# 03fpga.net
KiCad netlist of a schematic drawn in Altium Designer
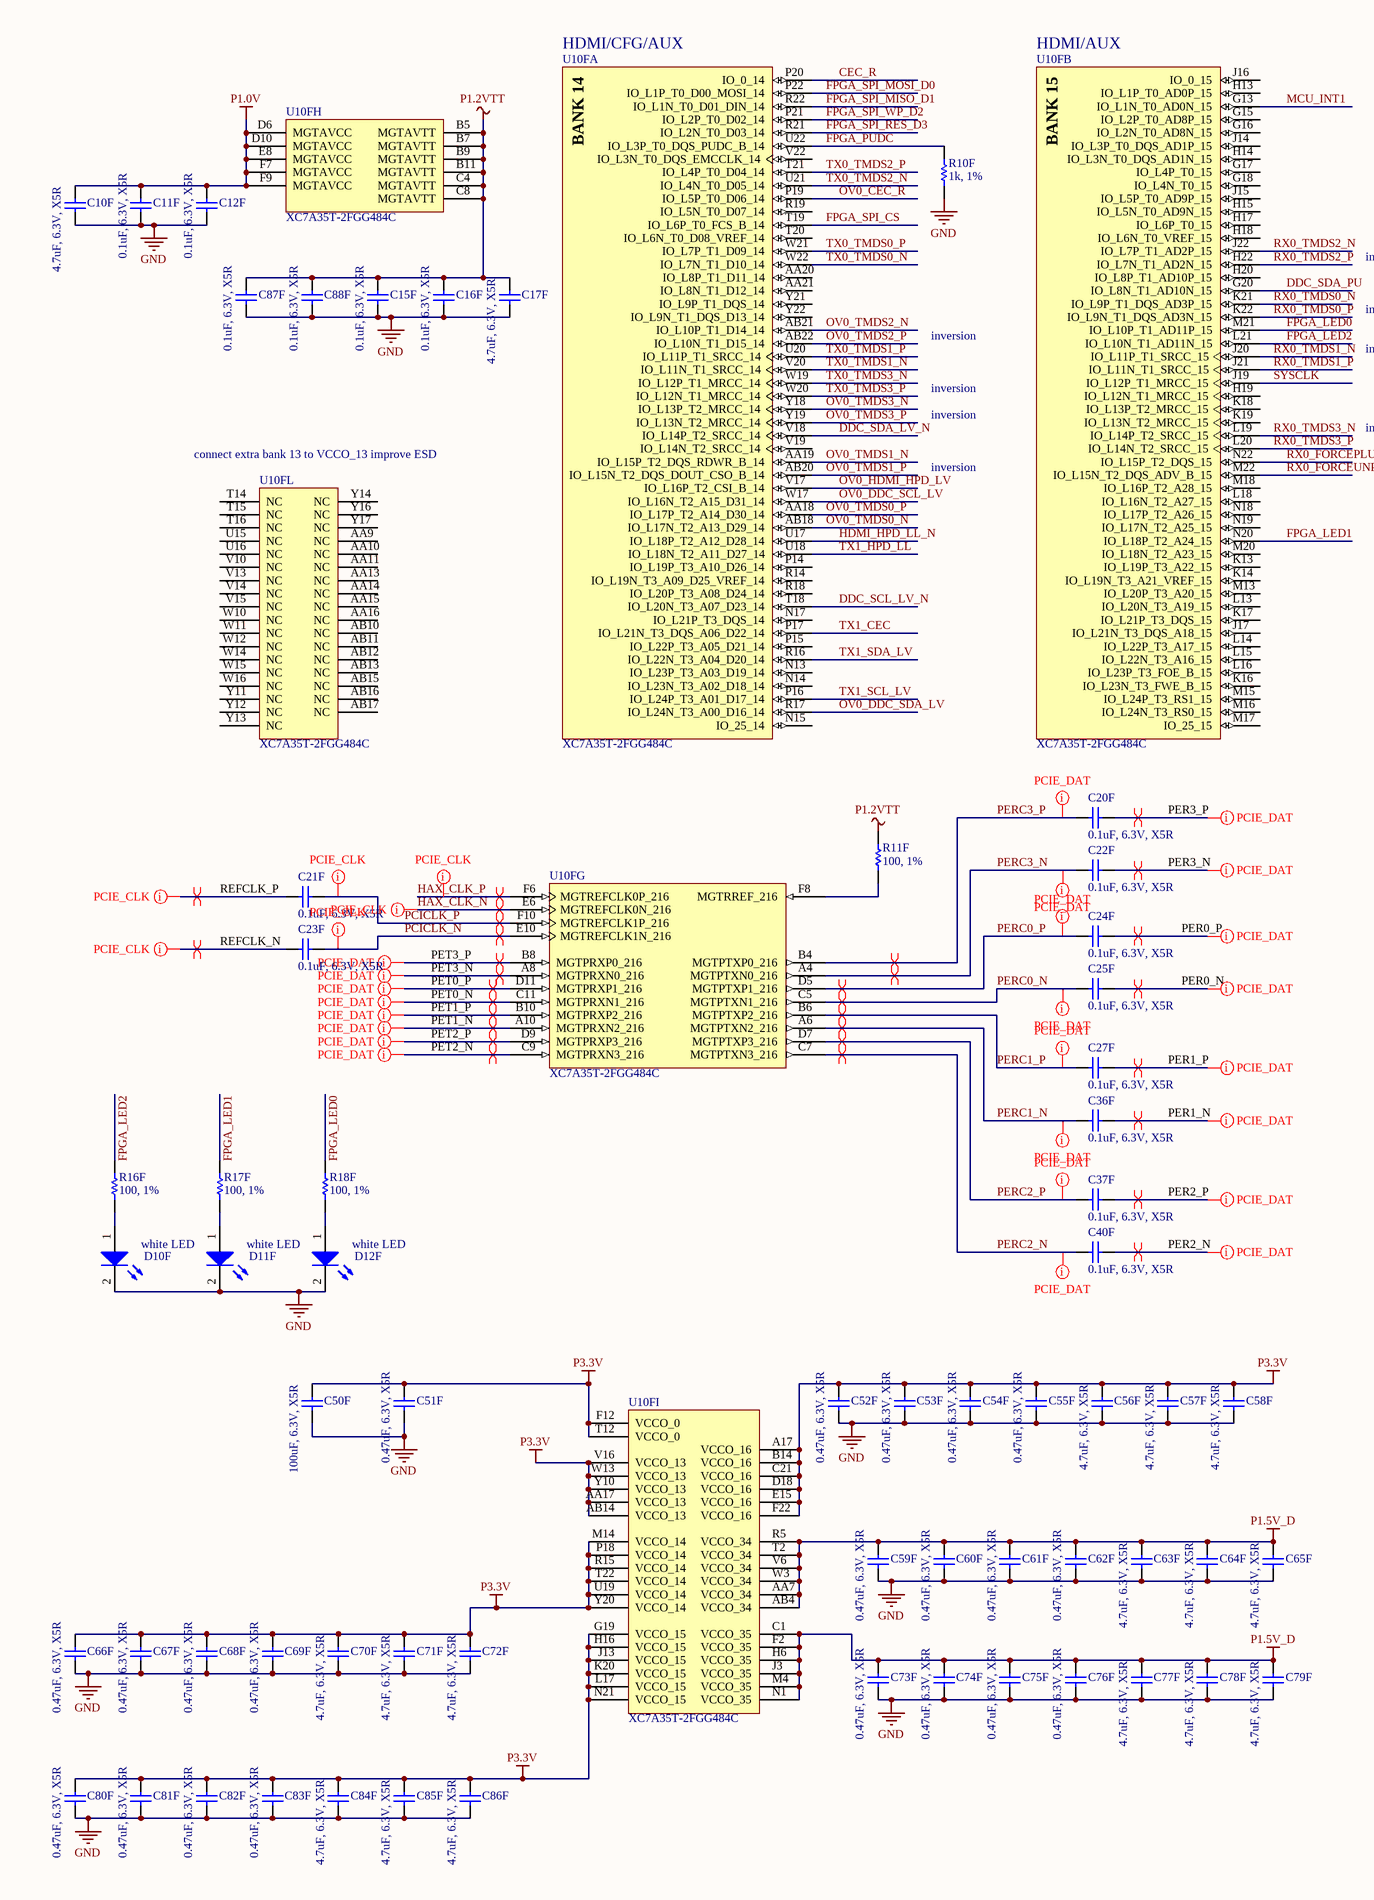
[diagram p0: 03fpga.SchDoc, left]
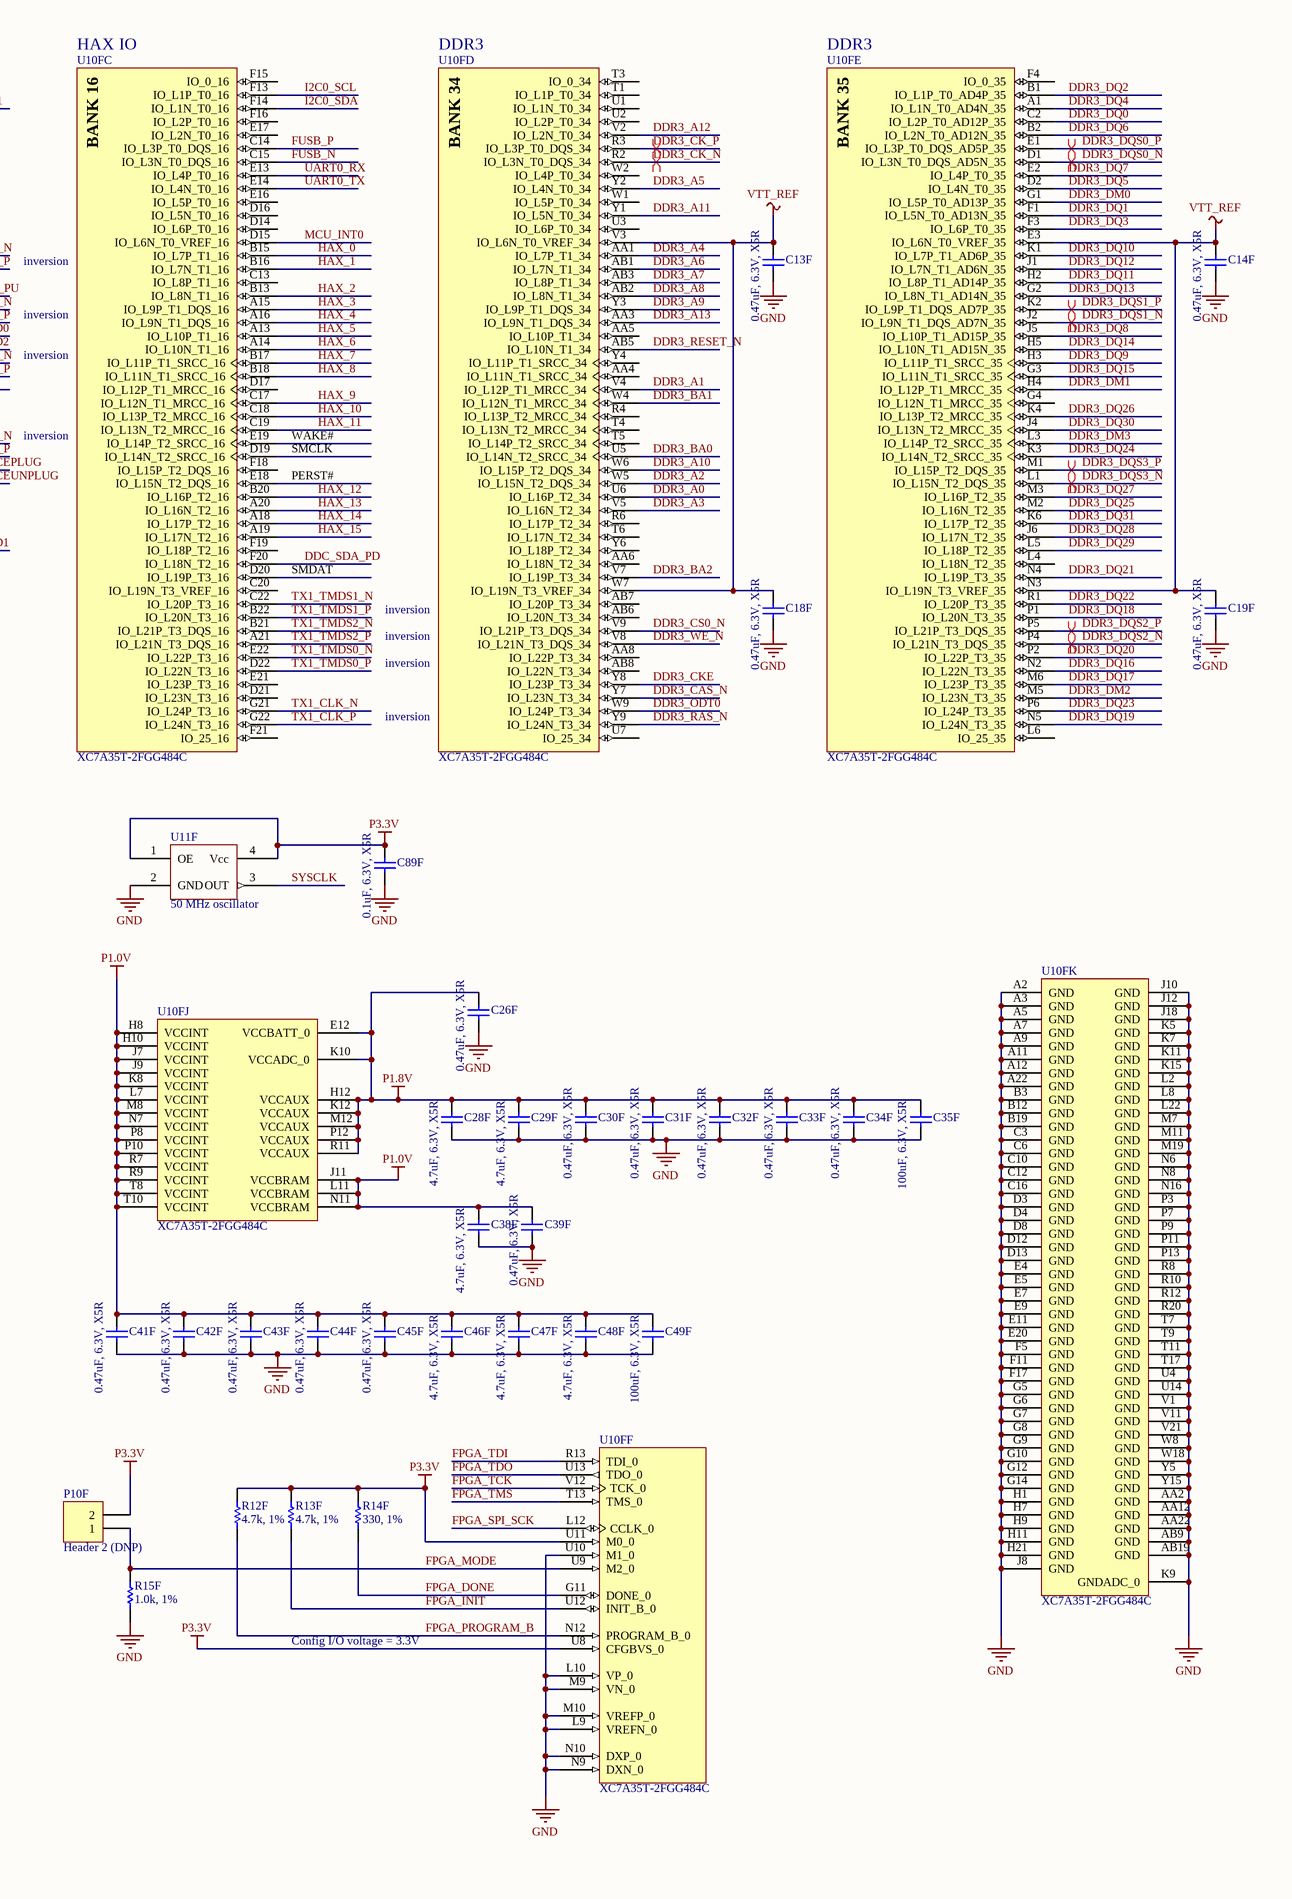
[diagram p1: 03fpga.SchDoc, right]

(export (version "E")
  (design (tool "Eeschema 10.0.6"))
  (components
    (comp (ref "C10F")
      (value "4.7uF, 6.3V, X5R")
      (footprint "CAPC1005N")
      (description "Capacitor (Semiconductor SIM Model)")
      (fields (field (name "MPN") "CL05A475MQ5NQNC"))
      (libsource (lib "Miscellaneous Devices") (part "Cap Semi"))
    )
    (comp (ref "C11F")
      (value "0.1uF, 6.3V, X5R")
      (footprint "CAPC0603X03L")
      (description "Capacitor (Semiconductor SIM Model)")
      (fields (field (name "MPN") "CL03A104KQ3NNNC"))
      (libsource (lib "Miscellaneous Devices") (part "Cap Semi"))
    )
    (comp (ref "C12F")
      (value "0.1uF, 6.3V, X5R")
      (footprint "CAPC0603X03L")
      (description "Capacitor (Semiconductor SIM Model)")
      (fields (field (name "MPN") "CL03A104KQ3NNNC"))
      (libsource (lib "Miscellaneous Devices") (part "Cap Semi"))
    )
    (comp (ref "C13F")
      (value "0.47uF, 6.3V, X5R")
      (footprint "CAPC0603X03L")
      (description "Capacitor (Semiconductor SIM Model)")
      (fields (field (name "MPN") "CL03A474KQ3NNNH"))
      (libsource (lib "Miscellaneous Devices") (part "Cap Semi"))
    )
    (comp (ref "C14F")
      (value "0.47uF, 6.3V, X5R")
      (footprint "CAPC0603X03L")
      (description "Capacitor (Semiconductor SIM Model)")
      (fields (field (name "MPN") "CL03A474KQ3NNNH"))
      (libsource (lib "Miscellaneous Devices") (part "Cap Semi"))
    )
    (comp (ref "C15F")
      (value "0.1uF, 6.3V, X5R")
      (footprint "CAPC0603X03L")
      (description "Capacitor (Semiconductor SIM Model)")
      (fields (field (name "MPN") "CL03A104KQ3NNNC"))
      (libsource (lib "Miscellaneous Devices") (part "Cap Semi"))
    )
    (comp (ref "C16F")
      (value "0.1uF, 6.3V, X5R")
      (footprint "CAPC0603X03L")
      (description "Capacitor (Semiconductor SIM Model)")
      (fields (field (name "MPN") "CL03A104KQ3NNNC"))
      (libsource (lib "Miscellaneous Devices") (part "Cap Semi"))
    )
    (comp (ref "C17F")
      (value "4.7uF, 6.3V, X5R")
      (footprint "CAPC1005N")
      (description "Capacitor (Semiconductor SIM Model)")
      (fields (field (name "MPN") "CL05A475MQ5NQNC"))
      (libsource (lib "Miscellaneous Devices") (part "Cap Semi"))
    )
    (comp (ref "C18F")
      (value "0.47uF, 6.3V, X5R")
      (footprint "CAPC0603X03L")
      (description "Capacitor (Semiconductor SIM Model)")
      (fields (field (name "MPN") "CL03A474KQ3NNNH"))
      (libsource (lib "Miscellaneous Devices") (part "Cap Semi"))
    )
    (comp (ref "C19F")
      (value "0.47uF, 6.3V, X5R")
      (footprint "CAPC0603X03L")
      (description "Capacitor (Semiconductor SIM Model)")
      (fields (field (name "MPN") "CL03A474KQ3NNNH"))
      (libsource (lib "Miscellaneous Devices") (part "Cap Semi"))
    )
    (comp (ref "C20F")
      (value "0.1uF, 6.3V, X5R")
      (footprint "CAPC0603X03L")
      (description "Capacitor (Semiconductor SIM Model)")
      (fields (field (name "MPN") "CL03A104KQ3NNNC"))
      (libsource (lib "Miscellaneous Devices") (part "Cap Semi"))
    )
    (comp (ref "C21F")
      (value "0.1uF, 6.3V, X5R")
      (footprint "CAPC0603X03L")
      (description "Capacitor (Semiconductor SIM Model)")
      (fields (field (name "MPN") "CL03A104KQ3NNNC"))
      (libsource (lib "Miscellaneous Devices") (part "Cap Semi"))
    )
    (comp (ref "C22F")
      (value "0.1uF, 6.3V, X5R")
      (footprint "CAPC0603X03L")
      (description "Capacitor (Semiconductor SIM Model)")
      (fields (field (name "MPN") "CL03A104KQ3NNNC"))
      (libsource (lib "Miscellaneous Devices") (part "Cap Semi"))
    )
    (comp (ref "C23F")
      (value "0.1uF, 6.3V, X5R")
      (footprint "CAPC0603X03L")
      (description "Capacitor (Semiconductor SIM Model)")
      (fields (field (name "MPN") "CL03A104KQ3NNNC"))
      (libsource (lib "Miscellaneous Devices") (part "Cap Semi"))
    )
    (comp (ref "C24F")
      (value "0.1uF, 6.3V, X5R")
      (footprint "CAPC0603X03L")
      (description "Capacitor (Semiconductor SIM Model)")
      (fields (field (name "MPN") "CL03A104KQ3NNNC"))
      (libsource (lib "Miscellaneous Devices") (part "Cap Semi"))
    )
    (comp (ref "C25F")
      (value "0.1uF, 6.3V, X5R")
      (footprint "CAPC0603X03L")
      (description "Capacitor (Semiconductor SIM Model)")
      (fields (field (name "MPN") "CL03A104KQ3NNNC"))
      (libsource (lib "Miscellaneous Devices") (part "Cap Semi"))
    )
    (comp (ref "C26F")
      (value "0.47uF, 6.3V, X5R")
      (footprint "CAPC0603X03L")
      (description "Capacitor (Semiconductor SIM Model)")
      (fields (field (name "MPN") "CL03A474KQ3NNNH"))
      (libsource (lib "Miscellaneous Devices") (part "Cap Semi"))
    )
    (comp (ref "C27F")
      (value "0.1uF, 6.3V, X5R")
      (footprint "CAPC0603X03L")
      (description "Capacitor (Semiconductor SIM Model)")
      (fields (field (name "MPN") "CL03A104KQ3NNNC"))
      (libsource (lib "Miscellaneous Devices") (part "Cap Semi"))
    )
    (comp (ref "C28F")
      (value "4.7uF, 6.3V, X5R")
      (footprint "CAPC1005N")
      (description "Capacitor (Semiconductor SIM Model)")
      (fields (field (name "MPN") "CL05A475MQ5NQNC"))
      (libsource (lib "Miscellaneous Devices") (part "Cap Semi"))
    )
    (comp (ref "C29F")
      (value "4.7uF, 6.3V, X5R")
      (footprint "CAPC1005N")
      (description "Capacitor (Semiconductor SIM Model)")
      (fields (field (name "MPN") "CL05A475MQ5NQNC"))
      (libsource (lib "Miscellaneous Devices") (part "Cap Semi"))
    )
    (comp (ref "C30F")
      (value "0.47uF, 6.3V, X5R")
      (footprint "CAPC0603X03L")
      (description "Capacitor (Semiconductor SIM Model)")
      (fields (field (name "MPN") "CL03A474KQ3NNNH"))
      (libsource (lib "Miscellaneous Devices") (part "Cap Semi"))
    )
    (comp (ref "C31F")
      (value "0.47uF, 6.3V, X5R")
      (footprint "CAPC0603X03L")
      (description "Capacitor (Semiconductor SIM Model)")
      (fields (field (name "MPN") "CL03A474KQ3NNNH"))
      (libsource (lib "Miscellaneous Devices") (part "Cap Semi"))
    )
    (comp (ref "C32F")
      (value "0.47uF, 6.3V, X5R")
      (footprint "CAPC0603X03L")
      (description "Capacitor (Semiconductor SIM Model)")
      (fields (field (name "MPN") "CL03A474KQ3NNNH"))
      (libsource (lib "Miscellaneous Devices") (part "Cap Semi"))
    )
    (comp (ref "C33F")
      (value "0.47uF, 6.3V, X5R")
      (footprint "CAPC0603X03L")
      (description "Capacitor (Semiconductor SIM Model)")
      (fields (field (name "MPN") "CL03A474KQ3NNNH"))
      (libsource (lib "Miscellaneous Devices") (part "Cap Semi"))
    )
    (comp (ref "C34F")
      (value "0.47uF, 6.3V, X5R")
      (footprint "CAPC0603X03L")
      (description "Capacitor (Semiconductor SIM Model)")
      (fields (field (name "MPN") "CL03A474KQ3NNNH"))
      (libsource (lib "Miscellaneous Devices") (part "Cap Semi"))
    )
    (comp (ref "C35F")
      (value "100uF, 6.3V, X5R")
      (footprint "CAPC3216N")
      (description "Capacitor (Semiconductor SIM Model)")
      (fields (field (name "MPN") "CL31A107MQHNNNE"))
      (libsource (lib "Miscellaneous Devices") (part "Cap Semi"))
    )
    (comp (ref "C36F")
      (value "0.1uF, 6.3V, X5R")
      (footprint "CAPC0603X03L")
      (description "Capacitor (Semiconductor SIM Model)")
      (fields (field (name "MPN") "CL03A104KQ3NNNC"))
      (libsource (lib "Miscellaneous Devices") (part "Cap Semi"))
    )
    (comp (ref "C37F")
      (value "0.1uF, 6.3V, X5R")
      (footprint "CAPC0603X03L")
      (description "Capacitor (Semiconductor SIM Model)")
      (fields (field (name "MPN") "CL03A104KQ3NNNC"))
      (libsource (lib "Miscellaneous Devices") (part "Cap Semi"))
    )
    (comp (ref "C38F")
      (value "4.7uF, 6.3V, X5R")
      (footprint "CAPC1005N")
      (description "Capacitor (Semiconductor SIM Model)")
      (fields (field (name "MPN") "CL05A475MQ5NQNC"))
      (libsource (lib "Miscellaneous Devices") (part "Cap Semi"))
    )
    (comp (ref "C39F")
      (value "0.47uF, 6.3V, X5R")
      (footprint "CAPC0603X03L")
      (description "Capacitor (Semiconductor SIM Model)")
      (fields (field (name "MPN") "CL03A474KQ3NNNH"))
      (libsource (lib "Miscellaneous Devices") (part "Cap Semi"))
    )
    (comp (ref "C40F")
      (value "0.1uF, 6.3V, X5R")
      (footprint "CAPC0603X03L")
      (description "Capacitor (Semiconductor SIM Model)")
      (fields (field (name "MPN") "CL03A104KQ3NNNC"))
      (libsource (lib "Miscellaneous Devices") (part "Cap Semi"))
    )
    (comp (ref "C41F")
      (value "0.47uF, 6.3V, X5R")
      (footprint "CAPC0603X03L")
      (description "Capacitor (Semiconductor SIM Model)")
      (fields (field (name "MPN") "CL03A474KQ3NNNH"))
      (libsource (lib "Miscellaneous Devices") (part "Cap Semi"))
    )
    (comp (ref "C42F")
      (value "0.47uF, 6.3V, X5R")
      (footprint "CAPC0603X03L")
      (description "Capacitor (Semiconductor SIM Model)")
      (fields (field (name "MPN") "CL03A474KQ3NNNH"))
      (libsource (lib "Miscellaneous Devices") (part "Cap Semi"))
    )
    (comp (ref "C43F")
      (value "0.47uF, 6.3V, X5R")
      (footprint "CAPC0603X03L")
      (description "Capacitor (Semiconductor SIM Model)")
      (fields (field (name "MPN") "CL03A474KQ3NNNH"))
      (libsource (lib "Miscellaneous Devices") (part "Cap Semi"))
    )
    (comp (ref "C44F")
      (value "0.47uF, 6.3V, X5R")
      (footprint "CAPC0603X03L")
      (description "Capacitor (Semiconductor SIM Model)")
      (fields (field (name "MPN") "CL03A474KQ3NNNH"))
      (libsource (lib "Miscellaneous Devices") (part "Cap Semi"))
    )
    (comp (ref "C45F")
      (value "0.47uF, 6.3V, X5R")
      (footprint "CAPC0603X03L")
      (description "Capacitor (Semiconductor SIM Model)")
      (fields (field (name "MPN") "CL03A474KQ3NNNH"))
      (libsource (lib "Miscellaneous Devices") (part "Cap Semi"))
    )
    (comp (ref "C46F")
      (value "4.7uF, 6.3V, X5R")
      (footprint "CAPC1005N")
      (description "Capacitor (Semiconductor SIM Model)")
      (fields (field (name "MPN") "CL05A475MQ5NQNC"))
      (libsource (lib "Miscellaneous Devices") (part "Cap Semi"))
    )
    (comp (ref "C47F")
      (value "4.7uF, 6.3V, X5R")
      (footprint "CAPC1005N")
      (description "Capacitor (Semiconductor SIM Model)")
      (fields (field (name "MPN") "CL05A475MQ5NQNC"))
      (libsource (lib "Miscellaneous Devices") (part "Cap Semi"))
    )
    (comp (ref "C48F")
      (value "4.7uF, 6.3V, X5R")
      (footprint "CAPC1005N")
      (description "Capacitor (Semiconductor SIM Model)")
      (fields (field (name "MPN") "CL05A475MQ5NQNC"))
      (libsource (lib "Miscellaneous Devices") (part "Cap Semi"))
    )
    (comp (ref "C49F")
      (value "100uF, 6.3V, X5R")
      (footprint "CAPC3216N")
      (description "Capacitor (Semiconductor SIM Model)")
      (fields (field (name "MPN") "CL31A107MQHNNNE"))
      (libsource (lib "Miscellaneous Devices") (part "Cap Semi"))
    )
    (comp (ref "C50F")
      (value "100uF, 6.3V, X5R")
      (footprint "CAPC3216N")
      (description "Capacitor (Semiconductor SIM Model)")
      (fields (field (name "MPN") "CL31A107MQHNNNE"))
      (libsource (lib "Miscellaneous Devices") (part "Cap Semi"))
    )
    (comp (ref "C51F")
      (value "0.47uF, 6.3V, X5R")
      (footprint "CAPC0603X03L")
      (description "Capacitor (Semiconductor SIM Model)")
      (fields (field (name "MPN") "CL03A474KQ3NNNH"))
      (libsource (lib "Miscellaneous Devices") (part "Cap Semi"))
    )
    (comp (ref "C52F")
      (value "0.47uF, 6.3V, X5R")
      (footprint "CAPC0603X03L")
      (description "Capacitor (Semiconductor SIM Model)")
      (fields (field (name "MPN") "CL03A474KQ3NNNH"))
      (libsource (lib "Miscellaneous Devices") (part "Cap Semi"))
    )
    (comp (ref "C53F")
      (value "0.47uF, 6.3V, X5R")
      (footprint "CAPC0603X03L")
      (description "Capacitor (Semiconductor SIM Model)")
      (fields (field (name "MPN") "CL03A474KQ3NNNH"))
      (libsource (lib "Miscellaneous Devices") (part "Cap Semi"))
    )
    (comp (ref "C54F")
      (value "0.47uF, 6.3V, X5R")
      (footprint "CAPC0603X03L")
      (description "Capacitor (Semiconductor SIM Model)")
      (fields (field (name "MPN") "CL03A474KQ3NNNH"))
      (libsource (lib "Miscellaneous Devices") (part "Cap Semi"))
    )
    (comp (ref "C55F")
      (value "0.47uF, 6.3V, X5R")
      (footprint "CAPC0603X03L")
      (description "Capacitor (Semiconductor SIM Model)")
      (fields (field (name "MPN") "CL03A474KQ3NNNH"))
      (libsource (lib "Miscellaneous Devices") (part "Cap Semi"))
    )
    (comp (ref "C56F")
      (value "4.7uF, 6.3V, X5R")
      (footprint "CAPC1005N")
      (description "Capacitor (Semiconductor SIM Model)")
      (fields (field (name "MPN") "CL05A475MQ5NQNC"))
      (libsource (lib "Miscellaneous Devices") (part "Cap Semi"))
    )
    (comp (ref "C57F")
      (value "4.7uF, 6.3V, X5R")
      (footprint "CAPC1005N")
      (description "Capacitor (Semiconductor SIM Model)")
      (fields (field (name "MPN") "CL05A475MQ5NQNC"))
      (libsource (lib "Miscellaneous Devices") (part "Cap Semi"))
    )
    (comp (ref "C58F")
      (value "4.7uF, 6.3V, X5R")
      (footprint "CAPC1005N")
      (description "Capacitor (Semiconductor SIM Model)")
      (fields (field (name "MPN") "CL05A475MQ5NQNC"))
      (libsource (lib "Miscellaneous Devices") (part "Cap Semi"))
    )
    (comp (ref "C59F")
      (value "0.47uF, 6.3V, X5R")
      (footprint "CAPC0603X03L")
      (description "Capacitor (Semiconductor SIM Model)")
      (fields (field (name "MPN") "CL03A474KQ3NNNH"))
      (libsource (lib "Miscellaneous Devices") (part "Cap Semi"))
    )
    (comp (ref "C60F")
      (value "0.47uF, 6.3V, X5R")
      (footprint "CAPC0603X03L")
      (description "Capacitor (Semiconductor SIM Model)")
      (fields (field (name "MPN") "CL03A474KQ3NNNH"))
      (libsource (lib "Miscellaneous Devices") (part "Cap Semi"))
    )
    (comp (ref "C61F")
      (value "0.47uF, 6.3V, X5R")
      (footprint "CAPC0603X03L")
      (description "Capacitor (Semiconductor SIM Model)")
      (fields (field (name "MPN") "CL03A474KQ3NNNH"))
      (libsource (lib "Miscellaneous Devices") (part "Cap Semi"))
    )
    (comp (ref "C62F")
      (value "0.47uF, 6.3V, X5R")
      (footprint "CAPC0603X03L")
      (description "Capacitor (Semiconductor SIM Model)")
      (fields (field (name "MPN") "CL03A474KQ3NNNH"))
      (libsource (lib "Miscellaneous Devices") (part "Cap Semi"))
    )
    (comp (ref "C63F")
      (value "4.7uF, 6.3V, X5R")
      (footprint "CAPC1005N")
      (description "Capacitor (Semiconductor SIM Model)")
      (fields (field (name "MPN") "CL05A475MQ5NQNC"))
      (libsource (lib "Miscellaneous Devices") (part "Cap Semi"))
    )
    (comp (ref "C64F")
      (value "4.7uF, 6.3V, X5R")
      (footprint "CAPC1005N")
      (description "Capacitor (Semiconductor SIM Model)")
      (fields (field (name "MPN") "CL05A475MQ5NQNC"))
      (libsource (lib "Miscellaneous Devices") (part "Cap Semi"))
    )
    (comp (ref "C65F")
      (value "4.7uF, 6.3V, X5R")
      (footprint "CAPC1005N")
      (description "Capacitor (Semiconductor SIM Model)")
      (fields (field (name "MPN") "CL05A475MQ5NQNC"))
      (libsource (lib "Miscellaneous Devices") (part "Cap Semi"))
    )
    (comp (ref "C66F")
      (value "0.47uF, 6.3V, X5R")
      (footprint "CAPC0603X03L")
      (description "Capacitor (Semiconductor SIM Model)")
      (fields (field (name "MPN") "CL03A474KQ3NNNH"))
      (libsource (lib "Miscellaneous Devices") (part "Cap Semi"))
    )
    (comp (ref "C67F")
      (value "0.47uF, 6.3V, X5R")
      (footprint "CAPC0603X03L")
      (description "Capacitor (Semiconductor SIM Model)")
      (fields (field (name "MPN") "CL03A474KQ3NNNH"))
      (libsource (lib "Miscellaneous Devices") (part "Cap Semi"))
    )
    (comp (ref "C68F")
      (value "0.47uF, 6.3V, X5R")
      (footprint "CAPC0603X03L")
      (description "Capacitor (Semiconductor SIM Model)")
      (fields (field (name "MPN") "CL03A474KQ3NNNH"))
      (libsource (lib "Miscellaneous Devices") (part "Cap Semi"))
    )
    (comp (ref "C69F")
      (value "0.47uF, 6.3V, X5R")
      (footprint "CAPC0603X03L")
      (description "Capacitor (Semiconductor SIM Model)")
      (fields (field (name "MPN") "CL03A474KQ3NNNH"))
      (libsource (lib "Miscellaneous Devices") (part "Cap Semi"))
    )
    (comp (ref "C70F")
      (value "4.7uF, 6.3V, X5R")
      (footprint "CAPC1005N")
      (description "Capacitor (Semiconductor SIM Model)")
      (fields (field (name "MPN") "CL05A475MQ5NQNC"))
      (libsource (lib "Miscellaneous Devices") (part "Cap Semi"))
    )
    (comp (ref "C71F")
      (value "4.7uF, 6.3V, X5R")
      (footprint "CAPC1005N")
      (description "Capacitor (Semiconductor SIM Model)")
      (fields (field (name "MPN") "CL05A475MQ5NQNC"))
      (libsource (lib "Miscellaneous Devices") (part "Cap Semi"))
    )
    (comp (ref "C72F")
      (value "4.7uF, 6.3V, X5R")
      (footprint "CAPC1005N")
      (description "Capacitor (Semiconductor SIM Model)")
      (fields (field (name "MPN") "CL05A475MQ5NQNC"))
      (libsource (lib "Miscellaneous Devices") (part "Cap Semi"))
    )
    (comp (ref "C73F")
      (value "0.47uF, 6.3V, X5R")
      (footprint "CAPC0603X03L")
      (description "Capacitor (Semiconductor SIM Model)")
      (fields (field (name "MPN") "CL03A474KQ3NNNH"))
      (libsource (lib "Miscellaneous Devices") (part "Cap Semi"))
    )
    (comp (ref "C74F")
      (value "0.47uF, 6.3V, X5R")
      (footprint "CAPC0603X03L")
      (description "Capacitor (Semiconductor SIM Model)")
      (fields (field (name "MPN") "CL03A474KQ3NNNH"))
      (libsource (lib "Miscellaneous Devices") (part "Cap Semi"))
    )
    (comp (ref "C75F")
      (value "0.47uF, 6.3V, X5R")
      (footprint "CAPC0603X03L")
      (description "Capacitor (Semiconductor SIM Model)")
      (fields (field (name "MPN") "CL03A474KQ3NNNH"))
      (libsource (lib "Miscellaneous Devices") (part "Cap Semi"))
    )
    (comp (ref "C76F")
      (value "0.47uF, 6.3V, X5R")
      (footprint "CAPC0603X03L")
      (description "Capacitor (Semiconductor SIM Model)")
      (fields (field (name "MPN") "CL03A474KQ3NNNH"))
      (libsource (lib "Miscellaneous Devices") (part "Cap Semi"))
    )
    (comp (ref "C77F")
      (value "4.7uF, 6.3V, X5R")
      (footprint "CAPC1005N")
      (description "Capacitor (Semiconductor SIM Model)")
      (fields (field (name "MPN") "CL05A475MQ5NQNC"))
      (libsource (lib "Miscellaneous Devices") (part "Cap Semi"))
    )
    (comp (ref "C78F")
      (value "4.7uF, 6.3V, X5R")
      (footprint "CAPC1005N")
      (description "Capacitor (Semiconductor SIM Model)")
      (fields (field (name "MPN") "CL05A475MQ5NQNC"))
      (libsource (lib "Miscellaneous Devices") (part "Cap Semi"))
    )
    (comp (ref "C79F")
      (value "4.7uF, 6.3V, X5R")
      (footprint "CAPC1005N")
      (description "Capacitor (Semiconductor SIM Model)")
      (fields (field (name "MPN") "CL05A475MQ5NQNC"))
      (libsource (lib "Miscellaneous Devices") (part "Cap Semi"))
    )
    (comp (ref "C80F")
      (value "0.47uF, 6.3V, X5R")
      (footprint "CAPC0603X03L")
      (description "Capacitor (Semiconductor SIM Model)")
      (fields (field (name "MPN") "CL03A474KQ3NNNH"))
      (libsource (lib "Miscellaneous Devices") (part "Cap Semi"))
    )
    (comp (ref "C81F")
      (value "0.47uF, 6.3V, X5R")
      (footprint "CAPC0603X03L")
      (description "Capacitor (Semiconductor SIM Model)")
      (fields (field (name "MPN") "CL03A474KQ3NNNH"))
      (libsource (lib "Miscellaneous Devices") (part "Cap Semi"))
    )
    (comp (ref "C82F")
      (value "0.47uF, 6.3V, X5R")
      (footprint "CAPC0603X03L")
      (description "Capacitor (Semiconductor SIM Model)")
      (fields (field (name "MPN") "CL03A474KQ3NNNH"))
      (libsource (lib "Miscellaneous Devices") (part "Cap Semi"))
    )
    (comp (ref "C83F")
      (value "0.47uF, 6.3V, X5R")
      (footprint "CAPC0603X03L")
      (description "Capacitor (Semiconductor SIM Model)")
      (fields (field (name "MPN") "CL03A474KQ3NNNH"))
      (libsource (lib "Miscellaneous Devices") (part "Cap Semi"))
    )
    (comp (ref "C84F")
      (value "4.7uF, 6.3V, X5R")
      (footprint "CAPC1005N")
      (description "Capacitor (Semiconductor SIM Model)")
      (fields (field (name "MPN") "CL05A475MQ5NQNC"))
      (libsource (lib "Miscellaneous Devices") (part "Cap Semi"))
    )
    (comp (ref "C85F")
      (value "4.7uF, 6.3V, X5R")
      (footprint "CAPC1005N")
      (description "Capacitor (Semiconductor SIM Model)")
      (fields (field (name "MPN") "CL05A475MQ5NQNC"))
      (libsource (lib "Miscellaneous Devices") (part "Cap Semi"))
    )
    (comp (ref "C86F")
      (value "4.7uF, 6.3V, X5R")
      (footprint "CAPC1005N")
      (description "Capacitor (Semiconductor SIM Model)")
      (fields (field (name "MPN") "CL05A475MQ5NQNC"))
      (libsource (lib "Miscellaneous Devices") (part "Cap Semi"))
    )
    (comp (ref "C87F")
      (value "0.1uF, 6.3V, X5R")
      (footprint "CAPC0603X03L")
      (description "Capacitor (Semiconductor SIM Model)")
      (fields (field (name "MPN") "CL03A104KQ3NNNC"))
      (libsource (lib "Miscellaneous Devices") (part "Cap Semi"))
    )
    (comp (ref "C88F")
      (value "0.1uF, 6.3V, X5R")
      (footprint "CAPC0603X03L")
      (description "Capacitor (Semiconductor SIM Model)")
      (fields (field (name "MPN") "CL03A104KQ3NNNC"))
      (libsource (lib "Miscellaneous Devices") (part "Cap Semi"))
    )
    (comp (ref "C89F")
      (value "0.1uF, 6.3V, X5R")
      (footprint "CAPC0603X03L")
      (description "Capacitor (Semiconductor SIM Model)")
      (fields (field (name "MPN") "CL03A104KQ3NNNC"))
      (libsource (lib "Miscellaneous Devices") (part "Cap Semi"))
    )
    (comp (ref "D10F")
      (value "white LED")
      (footprint "CD2012-0805")
      (description "Typical RED, GREEN, YELLOW, AMBER GaAs LED")
      (fields (field (name "MPN") "CB-2012QWC-P8"))
      (libsource (lib "Miscellaneous Devices") (part "LED2"))
    )
    (comp (ref "D11F")
      (value "white LED")
      (footprint "CD2012-0805")
      (description "Typical RED, GREEN, YELLOW, AMBER GaAs LED")
      (fields (field (name "MPN") "CB-2012QWC-P8"))
      (libsource (lib "Miscellaneous Devices") (part "LED2"))
    )
    (comp (ref "D12F")
      (value "white LED")
      (footprint "CD2012-0805")
      (description "Typical RED, GREEN, YELLOW, AMBER GaAs LED")
      (fields (field (name "MPN") "CB-2012QWC-P8"))
      (libsource (lib "Miscellaneous Devices") (part "LED2"))
    )
    (comp (ref "P10F")
      (value "Header 2 (DNP)")
      (footprint "HDR1X2")
      (description "Header, 2-Pin")
      (fields (field (name "MPN") "DNP") (field (name "PUBLISHER") "Altium Limited"))
      (libsource (lib "Miscellaneous Connectors") (part "Header 2"))
    )
    (comp (ref "R10F")
      (value "1k, 1%")
      (footprint "RESC1005N")
      (description "Resistor")
      (fields (field (name "MPN") "RS02U102FT"))
      (libsource (lib "Miscellaneous Devices") (part "Res1"))
    )
    (comp (ref "R11F")
      (value "100, 1%")
      (footprint "RESC1005N")
      (description "Resistor")
      (fields (field (name "MPN") "ANY"))
      (libsource (lib "Miscellaneous Devices") (part "Res1"))
    )
    (comp (ref "R12F")
      (value "4.7k, 1%")
      (footprint "RESC1005N")
      (description "Resistor")
      (fields (field (name "MPN") "ANY"))
      (libsource (lib "Miscellaneous Devices") (part "Res1"))
    )
    (comp (ref "R13F")
      (value "4.7k, 1%")
      (footprint "RESC1005N")
      (description "Resistor")
      (fields (field (name "MPN") "ANY"))
      (libsource (lib "Miscellaneous Devices") (part "Res1"))
    )
    (comp (ref "R14F")
      (value "330, 1%")
      (footprint "RESC1005N")
      (description "Resistor")
      (fields (field (name "MPN") "RS02U331FT"))
      (libsource (lib "Miscellaneous Devices") (part "Res1"))
    )
    (comp (ref "R15F")
      (value "1.0k, 1%")
      (footprint "RESC1005N")
      (description "Resistor")
      (fields (field (name "MPN") "ANY"))
      (libsource (lib "Miscellaneous Devices") (part "Res1"))
    )
    (comp (ref "R16F")
      (value "100, 1%")
      (footprint "RESC1005N")
      (description "Resistor")
      (fields (field (name "MPN") "RS02U101FT"))
      (libsource (lib "Miscellaneous Devices") (part "Res1"))
    )
    (comp (ref "R17F")
      (value "100, 1%")
      (footprint "RESC1005N")
      (description "Resistor")
      (fields (field (name "MPN") "RS02U101FT"))
      (libsource (lib "Miscellaneous Devices") (part "Res1"))
    )
    (comp (ref "R18F")
      (value "100, 1%")
      (footprint "RESC1005N")
      (description "Resistor")
      (fields (field (name "MPN") "RS02U101FT"))
      (libsource (lib "Miscellaneous Devices") (part "Res1"))
    )
    (comp (ref "U10F")
      (value "XC7A35T-2FGG484C")
      (footprint "FGG484")
      (description "Artix-7 FPGA, 250 User I/Os, 4 GTP, 484-Ball BGA, Speed Grade 2, Commercial Grade, Pb-Free")
      (fields (field (name "MANUFACTURER") "Xilinx"))
      (libsource (lib "Xilinx Artix-7") (part "XC7A35T-2FGG484C"))
    )
    (comp (ref "U11F")
      (value "50 MHz oscillator")
      (footprint "ABRACON_ASDMB")
      (description "Abracon ASDMB Miniature Oscillator")
      (fields (field (name "MPN") "ASDMB-50.000MHZ-LC-T"))
      (libsource (lib "commonsch") (part "OSCILLATOR"))
    )
  )
  (nets
    (net (code "1") (name "/CEC_R") (class "Default")
      (node (ref "U10F") (pin "P20") (pinfunction "IO_0_14_P20") (pintype "bidirectional"))
    )
    (net (code "2") (name "/DDC_SCL_LV_N") (class "Default")
      (node (ref "U10F") (pin "T18") (pinfunction "IO_L20N_T3_A07_D23_14_T18") (pintype "bidirectional"))
    )
    (net (code "3") (name "/DDC_SDA_LV_N") (class "Default")
      (node (ref "U10F") (pin "V18") (pinfunction "IO_L14P_T2_SRCC_14_V18") (pintype "bidirectional"))
    )
    (net (code "4") (name "/DDC_SDA_PD") (class "Default")
      (node (ref "U10F") (pin "F20") (pinfunction "IO_L18N_T2_16_F20") (pintype "bidirectional"))
    )
    (net (code "5") (name "/DDC_SDA_PU") (class "Default")
      (node (ref "U10F") (pin "G20") (pinfunction "IO_L8N_T1_AD10N_15_G20") (pintype "bidirectional"))
    )
    (net (code "6") (name "/DDR3_A0") (class "Default")
      (node (ref "U10F") (pin "U6") (pinfunction "IO_L16P_T2_34_U6") (pintype "bidirectional"))
    )
    (net (code "7") (name "/DDR3_A1") (class "Default")
      (node (ref "U10F") (pin "V4") (pinfunction "IO_L12P_T1_MRCC_34_V4") (pintype "bidirectional"))
    )
    (net (code "8") (name "/DDR3_A2") (class "Default")
      (node (ref "U10F") (pin "W5") (pinfunction "IO_L15N_T2_DQS_34_W5") (pintype "bidirectional"))
    )
    (net (code "9") (name "/DDR3_A3") (class "Default")
      (node (ref "U10F") (pin "V5") (pinfunction "IO_L16N_T2_34_V5") (pintype "bidirectional"))
    )
    (net (code "10") (name "/DDR3_A4") (class "Default")
      (node (ref "U10F") (pin "AA1") (pinfunction "IO_L7P_T1_34_AA1") (pintype "bidirectional"))
    )
    (net (code "11") (name "/DDR3_A5") (class "Default")
      (node (ref "U10F") (pin "Y2") (pinfunction "IO_L4N_T0_34_Y2") (pintype "bidirectional"))
    )
    (net (code "12") (name "/DDR3_A6") (class "Default")
      (node (ref "U10F") (pin "AB1") (pinfunction "IO_L7N_T1_34_AB1") (pintype "bidirectional"))
    )
    (net (code "13") (name "/DDR3_A7") (class "Default")
      (node (ref "U10F") (pin "AB3") (pinfunction "IO_L8P_T1_34_AB3") (pintype "bidirectional"))
    )
    (net (code "14") (name "/DDR3_A8") (class "Default")
      (node (ref "U10F") (pin "AB2") (pinfunction "IO_L8N_T1_34_AB2") (pintype "bidirectional"))
    )
    (net (code "15") (name "/DDR3_A9") (class "Default")
      (node (ref "U10F") (pin "Y3") (pinfunction "IO_L9P_T1_DQS_34_Y3") (pintype "bidirectional"))
    )
    (net (code "16") (name "/DDR3_A10") (class "Default")
      (node (ref "U10F") (pin "W6") (pinfunction "IO_L15P_T2_DQS_34_W6") (pintype "bidirectional"))
    )
    (net (code "17") (name "/DDR3_A11") (class "Default")
      (node (ref "U10F") (pin "Y1") (pinfunction "IO_L5N_T0_34_Y1") (pintype "bidirectional"))
    )
    (net (code "18") (name "/DDR3_A12") (class "Default")
      (node (ref "U10F") (pin "V2") (pinfunction "IO_L2N_T0_34_V2") (pintype "bidirectional"))
    )
    (net (code "19") (name "/DDR3_A13") (class "Default")
      (node (ref "U10F") (pin "AA3") (pinfunction "IO_L9N_T1_DQS_34_AA3") (pintype "bidirectional"))
    )
    (net (code "20") (name "/DDR3_BA0") (class "Default")
      (node (ref "U10F") (pin "U5") (pinfunction "IO_L14N_T2_SRCC_34_U5") (pintype "bidirectional"))
    )
    (net (code "21") (name "/DDR3_BA1") (class "Default")
      (node (ref "U10F") (pin "W4") (pinfunction "IO_L12N_T1_MRCC_34_W4") (pintype "bidirectional"))
    )
    (net (code "22") (name "/DDR3_BA2") (class "Default")
      (node (ref "U10F") (pin "V7") (pinfunction "IO_L19P_T3_34_V7") (pintype "bidirectional"))
    )
    (net (code "23") (name "/DDR3_CAS_N") (class "Default")
      (node (ref "U10F") (pin "Y7") (pinfunction "IO_L23N_T3_34_Y7") (pintype "bidirectional"))
    )
    (net (code "24") (name "/DDR3_CKE") (class "Default")
      (node (ref "U10F") (pin "Y8") (pinfunction "IO_L23P_T3_34_Y8") (pintype "bidirectional"))
    )
    (net (code "25") (name "/DDR3_CK_N") (class "Default")
      (node (ref "U10F") (pin "R2") (pinfunction "IO_L3N_T0_DQS_34_R2") (pintype "bidirectional"))
    )
    (net (code "26") (name "/DDR3_CK_P") (class "Default")
      (node (ref "U10F") (pin "R3") (pinfunction "IO_L3P_T0_DQS_34_R3") (pintype "bidirectional"))
    )
    (net (code "27") (name "/DDR3_CS0_N") (class "Default")
      (node (ref "U10F") (pin "V9") (pinfunction "IO_L21P_T3_DQS_34_V9") (pintype "bidirectional"))
    )
    (net (code "28") (name "/DDR3_DM0") (class "Default")
      (node (ref "U10F") (pin "G1") (pinfunction "IO_L5P_T0_AD13P_35_G1") (pintype "bidirectional"))
    )
    (net (code "29") (name "/DDR3_DM1") (class "Default")
      (node (ref "U10F") (pin "H4") (pinfunction "IO_L12P_T1_MRCC_35_H4") (pintype "bidirectional"))
    )
    (net (code "30") (name "/DDR3_DM2") (class "Default")
      (node (ref "U10F") (pin "M5") (pinfunction "IO_L23N_T3_35_M5") (pintype "bidirectional"))
    )
    (net (code "31") (name "/DDR3_DM3") (class "Default")
      (node (ref "U10F") (pin "L3") (pinfunction "IO_L14P_T2_SRCC_35_L3") (pintype "bidirectional"))
    )
    (net (code "32") (name "/DDR3_DQ0") (class "Default")
      (node (ref "U10F") (pin "C2") (pinfunction "IO_L2P_T0_AD12P_35_C2") (pintype "bidirectional"))
    )
    (net (code "33") (name "/DDR3_DQ1") (class "Default")
      (node (ref "U10F") (pin "F1") (pinfunction "IO_L5N_T0_AD13N_35_F1") (pintype "bidirectional"))
    )
    (net (code "34") (name "/DDR3_DQ2") (class "Default")
      (node (ref "U10F") (pin "B1") (pinfunction "IO_L1P_T0_AD4P_35_B1") (pintype "bidirectional"))
    )
    (net (code "35") (name "/DDR3_DQ3") (class "Default")
      (node (ref "U10F") (pin "F3") (pinfunction "IO_L6P_T0_35_F3") (pintype "bidirectional"))
    )
    (net (code "36") (name "/DDR3_DQ4") (class "Default")
      (node (ref "U10F") (pin "A1") (pinfunction "IO_L1N_T0_AD4N_35_A1") (pintype "bidirectional"))
    )
    (net (code "37") (name "/DDR3_DQ5") (class "Default")
      (node (ref "U10F") (pin "D2") (pinfunction "IO_L4N_T0_35_D2") (pintype "bidirectional"))
    )
    (net (code "38") (name "/DDR3_DQ6") (class "Default")
      (node (ref "U10F") (pin "B2") (pinfunction "IO_L2N_T0_AD12N_35_B2") (pintype "bidirectional"))
    )
    (net (code "39") (name "/DDR3_DQ7") (class "Default")
      (node (ref "U10F") (pin "E2") (pinfunction "IO_L4P_T0_35_E2") (pintype "bidirectional"))
    )
    (net (code "40") (name "/DDR3_DQ8") (class "Default")
      (node (ref "U10F") (pin "J5") (pinfunction "IO_L10P_T1_AD15P_35_J5") (pintype "bidirectional"))
    )
    (net (code "41") (name "/DDR3_DQ9") (class "Default")
      (node (ref "U10F") (pin "H3") (pinfunction "IO_L11P_T1_SRCC_35_H3") (pintype "bidirectional"))
    )
    (net (code "42") (name "/DDR3_DQ10") (class "Default")
      (node (ref "U10F") (pin "K1") (pinfunction "IO_L7P_T1_AD6P_35_K1") (pintype "bidirectional"))
    )
    (net (code "43") (name "/DDR3_DQ11") (class "Default")
      (node (ref "U10F") (pin "H2") (pinfunction "IO_L8P_T1_AD14P_35_H2") (pintype "bidirectional"))
    )
    (net (code "44") (name "/DDR3_DQ12") (class "Default")
      (node (ref "U10F") (pin "J1") (pinfunction "IO_L7N_T1_AD6N_35_J1") (pintype "bidirectional"))
    )
    (net (code "45") (name "/DDR3_DQ13") (class "Default")
      (node (ref "U10F") (pin "G2") (pinfunction "IO_L8N_T1_AD14N_35_G2") (pintype "bidirectional"))
    )
    (net (code "46") (name "/DDR3_DQ14") (class "Default")
      (node (ref "U10F") (pin "H5") (pinfunction "IO_L10N_T1_AD15N_35_H5") (pintype "bidirectional"))
    )
    (net (code "47") (name "/DDR3_DQ15") (class "Default")
      (node (ref "U10F") (pin "G3") (pinfunction "IO_L11N_T1_SRCC_35_G3") (pintype "bidirectional"))
    )
    (net (code "48") (name "/DDR3_DQ16") (class "Default")
      (node (ref "U10F") (pin "N2") (pinfunction "IO_L22N_T3_35_N2") (pintype "bidirectional"))
    )
    (net (code "49") (name "/DDR3_DQ17") (class "Default")
      (node (ref "U10F") (pin "M6") (pinfunction "IO_L23P_T3_35_M6") (pintype "bidirectional"))
    )
    (net (code "50") (name "/DDR3_DQ18") (class "Default")
      (node (ref "U10F") (pin "P1") (pinfunction "IO_L20N_T3_35_P1") (pintype "bidirectional"))
    )
    (net (code "51") (name "/DDR3_DQ19") (class "Default")
      (node (ref "U10F") (pin "N5") (pinfunction "IO_L24N_T3_35_N5") (pintype "bidirectional"))
    )
    (net (code "52") (name "/DDR3_DQ20") (class "Default")
      (node (ref "U10F") (pin "P2") (pinfunction "IO_L22P_T3_35_P2") (pintype "bidirectional"))
    )
    (net (code "53") (name "/DDR3_DQ21") (class "Default")
      (node (ref "U10F") (pin "N4") (pinfunction "IO_L19P_T3_35_N4") (pintype "bidirectional"))
    )
    (net (code "54") (name "/DDR3_DQ22") (class "Default")
      (node (ref "U10F") (pin "R1") (pinfunction "IO_L20P_T3_35_R1") (pintype "bidirectional"))
    )
    (net (code "55") (name "/DDR3_DQ23") (class "Default")
      (node (ref "U10F") (pin "P6") (pinfunction "IO_L24P_T3_35_P6") (pintype "bidirectional"))
    )
    (net (code "56") (name "/DDR3_DQ24") (class "Default")
      (node (ref "U10F") (pin "K3") (pinfunction "IO_L14N_T2_SRCC_35_K3") (pintype "bidirectional"))
    )
    (net (code "57") (name "/DDR3_DQ25") (class "Default")
      (node (ref "U10F") (pin "M2") (pinfunction "IO_L16N_T2_35_M2") (pintype "bidirectional"))
    )
    (net (code "58") (name "/DDR3_DQ26") (class "Default")
      (node (ref "U10F") (pin "K4") (pinfunction "IO_L13P_T2_MRCC_35_K4") (pintype "bidirectional"))
    )
    (net (code "59") (name "/DDR3_DQ27") (class "Default")
      (node (ref "U10F") (pin "M3") (pinfunction "IO_L16P_T2_35_M3") (pintype "bidirectional"))
    )
    (net (code "60") (name "/DDR3_DQ28") (class "Default")
      (node (ref "U10F") (pin "J6") (pinfunction "IO_L17N_T2_35_J6") (pintype "bidirectional"))
    )
    (net (code "61") (name "/DDR3_DQ29") (class "Default")
      (node (ref "U10F") (pin "L5") (pinfunction "IO_L18P_T2_35_L5") (pintype "bidirectional"))
    )
    (net (code "62") (name "/DDR3_DQ30") (class "Default")
      (node (ref "U10F") (pin "J4") (pinfunction "IO_L13N_T2_MRCC_35_J4") (pintype "bidirectional"))
    )
    (net (code "63") (name "/DDR3_DQ31") (class "Default")
      (node (ref "U10F") (pin "K6") (pinfunction "IO_L17P_T2_35_K6") (pintype "bidirectional"))
    )
    (net (code "64") (name "/DDR3_DQS0_N") (class "Default")
      (node (ref "U10F") (pin "D1") (pinfunction "IO_L3N_T0_DQS_AD5N_35_D1") (pintype "bidirectional"))
    )
    (net (code "65") (name "/DDR3_DQS0_P") (class "Default")
      (node (ref "U10F") (pin "E1") (pinfunction "IO_L3P_T0_DQS_AD5P_35_E1") (pintype "bidirectional"))
    )
    (net (code "66") (name "/DDR3_DQS1_N") (class "Default")
      (node (ref "U10F") (pin "J2") (pinfunction "IO_L9N_T1_DQS_AD7N_35_J2") (pintype "bidirectional"))
    )
    (net (code "67") (name "/DDR3_DQS1_P") (class "Default")
      (node (ref "U10F") (pin "K2") (pinfunction "IO_L9P_T1_DQS_AD7P_35_K2") (pintype "bidirectional"))
    )
    (net (code "68") (name "/DDR3_DQS2_N") (class "Default")
      (node (ref "U10F") (pin "P4") (pinfunction "IO_L21N_T3_DQS_35_P4") (pintype "bidirectional"))
    )
    (net (code "69") (name "/DDR3_DQS2_P") (class "Default")
      (node (ref "U10F") (pin "P5") (pinfunction "IO_L21P_T3_DQS_35_P5") (pintype "bidirectional"))
    )
    (net (code "70") (name "/DDR3_DQS3_N") (class "Default")
      (node (ref "U10F") (pin "L1") (pinfunction "IO_L15N_T2_DQS_35_L1") (pintype "bidirectional"))
    )
    (net (code "71") (name "/DDR3_DQS3_P") (class "Default")
      (node (ref "U10F") (pin "M1") (pinfunction "IO_L15P_T2_DQS_35_M1") (pintype "bidirectional"))
    )
    (net (code "72") (name "/DDR3_ODT0") (class "Default")
      (node (ref "U10F") (pin "W9") (pinfunction "IO_L24P_T3_34_W9") (pintype "bidirectional"))
    )
    (net (code "73") (name "/DDR3_RAS_N") (class "Default")
      (node (ref "U10F") (pin "Y9") (pinfunction "IO_L24N_T3_34_Y9") (pintype "bidirectional"))
    )
    (net (code "74") (name "/DDR3_RESET_N") (class "Default")
      (node (ref "U10F") (pin "AB5") (pinfunction "IO_L10N_T1_34_AB5") (pintype "bidirectional"))
    )
    (net (code "75") (name "/DDR3_WE_N") (class "Default")
      (node (ref "U10F") (pin "V8") (pinfunction "IO_L21N_T3_DQS_34_V8") (pintype "bidirectional"))
    )
    (net (code "76") (name "/FPGA_DONE") (class "Default")
      (node (ref "R14F") (pin "1") (pinfunction "1_1") (pintype "passive"))
      (node (ref "U10F") (pin "G11") (pinfunction "DONE_0_G11") (pintype "bidirectional"))
    )
    (net (code "77") (name "/FPGA_INIT") (class "Default")
      (node (ref "R13F") (pin "1") (pinfunction "1_1") (pintype "passive"))
      (node (ref "U10F") (pin "U12") (pinfunction "INIT_B_0_U12") (pintype "bidirectional"))
    )
    (net (code "78") (name "/FPGA_LED0") (class "Default")
      (node (ref "R18F") (pin "2") (pinfunction "2_2") (pintype "passive"))
      (node (ref "U10F") (pin "M21") (pinfunction "IO_L10P_T1_AD11P_15_M21") (pintype "bidirectional"))
    )
    (net (code "79") (name "/FPGA_LED1") (class "Default")
      (node (ref "R17F") (pin "2") (pinfunction "2_2") (pintype "passive"))
      (node (ref "U10F") (pin "N20") (pinfunction "IO_L18P_T2_A24_15_N20") (pintype "bidirectional"))
    )
    (net (code "80") (name "/FPGA_LED2") (class "Default")
      (node (ref "R16F") (pin "2") (pinfunction "2_2") (pintype "passive"))
      (node (ref "U10F") (pin "L21") (pinfunction "IO_L10N_T1_AD11N_15_L21") (pintype "bidirectional"))
    )
    (net (code "81") (name "/FPGA_MODE") (class "Default")
      (node (ref "P10F") (pin "1") (pinfunction "1_1") (pintype "passive"))
      (node (ref "R15F") (pin "2") (pinfunction "2_2") (pintype "passive"))
      (node (ref "U10F") (pin "U9") (pinfunction "M2_0_U9") (pintype "input"))
    )
    (net (code "82") (name "/FPGA_PROGRAM_B") (class "Default")
      (node (ref "R12F") (pin "1") (pinfunction "1_1") (pintype "passive"))
      (node (ref "U10F") (pin "N12") (pinfunction "PROGRAM_B_0_N12") (pintype "input"))
    )
    (net (code "83") (name "/FPGA_PUDC") (class "Default")
      (node (ref "R10F") (pin "1") (pinfunction "1_1") (pintype "passive"))
      (node (ref "U10F") (pin "U22") (pinfunction "IO_L3P_T0_DQS_PUDC_B_14_U22") (pintype "bidirectional"))
    )
    (net (code "84") (name "/FPGA_SPI_CS") (class "Default")
      (node (ref "U10F") (pin "T19") (pinfunction "IO_L6P_T0_FCS_B_14_T19") (pintype "bidirectional"))
    )
    (net (code "85") (name "/FPGA_SPI_MISO_D1") (class "Default")
      (node (ref "U10F") (pin "R22") (pinfunction "IO_L1N_T0_D01_DIN_14_R22") (pintype "bidirectional"))
    )
    (net (code "86") (name "/FPGA_SPI_MOSI_D0") (class "Default")
      (node (ref "U10F") (pin "P22") (pinfunction "IO_L1P_T0_D00_MOSI_14_P22") (pintype "bidirectional"))
    )
    (net (code "87") (name "/FPGA_SPI_RES_D3") (class "Default")
      (node (ref "U10F") (pin "R21") (pinfunction "IO_L2N_T0_D03_14_R21") (pintype "bidirectional"))
    )
    (net (code "88") (name "/FPGA_SPI_SCK") (class "Default")
      (node (ref "U10F") (pin "L12") (pinfunction "CCLK_0_L12") (pintype "bidirectional"))
    )
    (net (code "89") (name "/FPGA_SPI_WP_D2") (class "Default")
      (node (ref "U10F") (pin "P21") (pinfunction "IO_L2P_T0_D02_14_P21") (pintype "bidirectional"))
    )
    (net (code "90") (name "/FPGA_TCK") (class "Default")
      (node (ref "U10F") (pin "V12") (pinfunction "TCK_0_V12") (pintype "input"))
    )
    (net (code "91") (name "/FPGA_TDI") (class "Default")
      (node (ref "U10F") (pin "R13") (pinfunction "TDI_0_R13") (pintype "input"))
    )
    (net (code "92") (name "/FPGA_TDO") (class "Default")
      (node (ref "U10F") (pin "U13") (pinfunction "TDO_0_U13") (pintype "output"))
    )
    (net (code "93") (name "/FPGA_TMS") (class "Default")
      (node (ref "U10F") (pin "T13") (pinfunction "TMS_0_T13") (pintype "input"))
    )
    (net (code "94") (name "/FUSB_N") (class "Default")
      (node (ref "U10F") (pin "C15") (pinfunction "IO_L3N_T0_DQS_16_C15") (pintype "bidirectional"))
    )
    (net (code "95") (name "/FUSB_P") (class "Default")
      (node (ref "U10F") (pin "C14") (pinfunction "IO_L3P_T0_DQS_16_C14") (pintype "bidirectional"))
    )
    (net (code "96") (name "/HAX_0") (class "Default")
      (node (ref "U10F") (pin "B15") (pinfunction "IO_L7P_T1_16_B15") (pintype "bidirectional"))
    )
    (net (code "97") (name "/HAX_1") (class "Default")
      (node (ref "U10F") (pin "B16") (pinfunction "IO_L7N_T1_16_B16") (pintype "bidirectional"))
    )
    (net (code "98") (name "/HAX_2") (class "Default")
      (node (ref "U10F") (pin "B13") (pinfunction "IO_L8N_T1_16_B13") (pintype "bidirectional"))
    )
    (net (code "99") (name "/HAX_3") (class "Default")
      (node (ref "U10F") (pin "A15") (pinfunction "IO_L9P_T1_DQS_16_A15") (pintype "bidirectional"))
    )
    (net (code "100") (name "/HAX_4") (class "Default")
      (node (ref "U10F") (pin "A16") (pinfunction "IO_L9N_T1_DQS_16_A16") (pintype "bidirectional"))
    )
    (net (code "101") (name "/HAX_5") (class "Default")
      (node (ref "U10F") (pin "A13") (pinfunction "IO_L10P_T1_16_A13") (pintype "bidirectional"))
    )
    (net (code "102") (name "/HAX_6") (class "Default")
      (node (ref "U10F") (pin "A14") (pinfunction "IO_L10N_T1_16_A14") (pintype "bidirectional"))
    )
    (net (code "103") (name "/HAX_7") (class "Default")
      (node (ref "U10F") (pin "B17") (pinfunction "IO_L11P_T1_SRCC_16_B17") (pintype "bidirectional"))
    )
    (net (code "104") (name "/HAX_8") (class "Default")
      (node (ref "U10F") (pin "B18") (pinfunction "IO_L11N_T1_SRCC_16_B18") (pintype "bidirectional"))
    )
    (net (code "105") (name "/HAX_9") (class "Default")
      (node (ref "U10F") (pin "C17") (pinfunction "IO_L12N_T1_MRCC_16_C17") (pintype "bidirectional"))
    )
    (net (code "106") (name "/HAX_10") (class "Default")
      (node (ref "U10F") (pin "C18") (pinfunction "IO_L13P_T2_MRCC_16_C18") (pintype "bidirectional"))
    )
    (net (code "107") (name "/HAX_11") (class "Default")
      (node (ref "U10F") (pin "C19") (pinfunction "IO_L13N_T2_MRCC_16_C19") (pintype "bidirectional"))
    )
    (net (code "108") (name "/HAX_12") (class "Default")
      (node (ref "U10F") (pin "B20") (pinfunction "IO_L16P_T2_16_B20") (pintype "bidirectional"))
    )
    (net (code "109") (name "/HAX_13") (class "Default")
      (node (ref "U10F") (pin "A20") (pinfunction "IO_L16N_T2_16_A20") (pintype "bidirectional"))
    )
    (net (code "110") (name "/HAX_14") (class "Default")
      (node (ref "U10F") (pin "A18") (pinfunction "IO_L17P_T2_16_A18") (pintype "bidirectional"))
    )
    (net (code "111") (name "/HAX_15") (class "Default")
      (node (ref "U10F") (pin "A19") (pinfunction "IO_L17N_T2_16_A19") (pintype "bidirectional"))
    )
    (net (code "112") (name "/HAX_CLK_N") (class "Default")
      (node (ref "U10F") (pin "E6") (pinfunction "MGTREFCLK0N_216_E6") (pintype "input"))
    )
    (net (code "113") (name "/HAX_CLK_P") (class "Default")
      (node (ref "U10F") (pin "F6") (pinfunction "MGTREFCLK0P_216_F6") (pintype "input"))
    )
    (net (code "114") (name "/HDMI_HPD_LL_N") (class "Default")
      (node (ref "U10F") (pin "U17") (pinfunction "IO_L18P_T2_A12_D28_14_U17") (pintype "bidirectional"))
    )
    (net (code "115") (name "/I2C0_SCL") (class "Default")
      (node (ref "U10F") (pin "F13") (pinfunction "IO_L1P_T0_16_F13") (pintype "bidirectional"))
    )
    (net (code "116") (name "/I2C0_SDA") (class "Default")
      (node (ref "U10F") (pin "F14") (pinfunction "IO_L1N_T0_16_F14") (pintype "bidirectional"))
    )
    (net (code "117") (name "/MCU_INT0") (class "Default")
      (node (ref "U10F") (pin "D15") (pinfunction "IO_L6N_T0_VREF_16_D15") (pintype "bidirectional"))
    )
    (net (code "118") (name "/MCU_INT1") (class "Default")
      (node (ref "U10F") (pin "G13") (pinfunction "IO_L1N_T0_AD0N_15_G13") (pintype "bidirectional"))
    )
    (net (code "119") (name "/OV0_CEC_R") (class "Default")
      (node (ref "U10F") (pin "P19") (pinfunction "IO_L5P_T0_D06_14_P19") (pintype "bidirectional"))
    )
    (net (code "120") (name "/OV0_DDC_SCL_LV") (class "Default")
      (node (ref "U10F") (pin "W17") (pinfunction "IO_L16N_T2_A15_D31_14_W17") (pintype "bidirectional"))
    )
    (net (code "121") (name "/OV0_DDC_SDA_LV") (class "Default")
      (node (ref "U10F") (pin "R17") (pinfunction "IO_L24N_T3_A00_D16_14_R17") (pintype "bidirectional"))
    )
    (net (code "122") (name "/OV0_HDMI_HPD_LV") (class "Default")
      (node (ref "U10F") (pin "V17") (pinfunction "IO_L16P_T2_CSI_B_14_V17") (pintype "bidirectional"))
    )
    (net (code "123") (name "/OV0_TMDS0_N") (class "Default")
      (node (ref "U10F") (pin "AB18") (pinfunction "IO_L17N_T2_A13_D29_14_AB18") (pintype "bidirectional"))
    )
    (net (code "124") (name "/OV0_TMDS0_P") (class "Default")
      (node (ref "U10F") (pin "AA18") (pinfunction "IO_L17P_T2_A14_D30_14_AA18") (pintype "bidirectional"))
    )
    (net (code "125") (name "/OV0_TMDS1_N") (class "Default")
      (node (ref "U10F") (pin "AA19") (pinfunction "IO_L15P_T2_DQS_RDWR_B_14_AA19") (pintype "bidirectional"))
    )
    (net (code "126") (name "/OV0_TMDS1_P") (class "Default")
      (node (ref "U10F") (pin "AB20") (pinfunction "IO_L15N_T2_DQS_DOUT_CSO_B_14_AB20") (pintype "bidirectional"))
    )
    (net (code "127") (name "/OV0_TMDS2_N") (class "Default")
      (node (ref "U10F") (pin "AB21") (pinfunction "IO_L10P_T1_D14_14_AB21") (pintype "bidirectional"))
    )
    (net (code "128") (name "/OV0_TMDS2_P") (class "Default")
      (node (ref "U10F") (pin "AB22") (pinfunction "IO_L10N_T1_D15_14_AB22") (pintype "bidirectional"))
    )
    (net (code "129") (name "/OV0_TMDS3_N") (class "Default")
      (node (ref "U10F") (pin "Y18") (pinfunction "IO_L13P_T2_MRCC_14_Y18") (pintype "bidirectional"))
    )
    (net (code "130") (name "/OV0_TMDS3_P") (class "Default")
      (node (ref "U10F") (pin "Y19") (pinfunction "IO_L13N_T2_MRCC_14_Y19") (pintype "bidirectional"))
    )
    (net (code "131") (name "/PCICLK_N") (class "Default")
      (node (ref "C23F") (pin "1") (pinfunction "1_1") (pintype "passive"))
      (node (ref "U10F") (pin "E10") (pinfunction "MGTREFCLK1N_216_E10") (pintype "input"))
    )
    (net (code "132") (name "/PCICLK_P") (class "Default")
      (node (ref "C21F") (pin "1") (pinfunction "1_1") (pintype "passive"))
      (node (ref "U10F") (pin "F10") (pinfunction "MGTREFCLK1P_216_F10") (pintype "input"))
    )
    (net (code "133") (name "/PER0_N") (class "Default")
      (node (ref "C25F") (pin "1") (pinfunction "1_1") (pintype "passive"))
    )
    (net (code "134") (name "/PER0_P") (class "Default")
      (node (ref "C24F") (pin "1") (pinfunction "1_1") (pintype "passive"))
    )
    (net (code "135") (name "/PER1_N") (class "Default")
      (node (ref "C36F") (pin "1") (pinfunction "1_1") (pintype "passive"))
    )
    (net (code "136") (name "/PER1_P") (class "Default")
      (node (ref "C27F") (pin "1") (pinfunction "1_1") (pintype "passive"))
    )
    (net (code "137") (name "/PER2_N") (class "Default")
      (node (ref "C40F") (pin "1") (pinfunction "1_1") (pintype "passive"))
    )
    (net (code "138") (name "/PER2_P") (class "Default")
      (node (ref "C37F") (pin "1") (pinfunction "1_1") (pintype "passive"))
    )
    (net (code "139") (name "/PER3_N") (class "Default")
      (node (ref "C22F") (pin "1") (pinfunction "1_1") (pintype "passive"))
    )
    (net (code "140") (name "/PER3_P") (class "Default")
      (node (ref "C20F") (pin "1") (pinfunction "1_1") (pintype "passive"))
    )
    (net (code "141") (name "/PERC0_N") (class "Default")
      (node (ref "C25F") (pin "2") (pinfunction "2_2") (pintype "passive"))
      (node (ref "U10F") (pin "C5") (pinfunction "MGTPTXN1_216_C5") (pintype "output"))
    )
    (net (code "142") (name "/PERC0_P") (class "Default")
      (node (ref "C24F") (pin "2") (pinfunction "2_2") (pintype "passive"))
      (node (ref "U10F") (pin "D5") (pinfunction "MGTPTXP1_216_D5") (pintype "output"))
    )
    (net (code "143") (name "/PERC1_N") (class "Default")
      (node (ref "C36F") (pin "2") (pinfunction "2_2") (pintype "passive"))
      (node (ref "U10F") (pin "A6") (pinfunction "MGTPTXN2_216_A6") (pintype "output"))
    )
    (net (code "144") (name "/PERC1_P") (class "Default")
      (node (ref "C27F") (pin "2") (pinfunction "2_2") (pintype "passive"))
      (node (ref "U10F") (pin "B6") (pinfunction "MGTPTXP2_216_B6") (pintype "output"))
    )
    (net (code "145") (name "/PERC2_N") (class "Default")
      (node (ref "C40F") (pin "2") (pinfunction "2_2") (pintype "passive"))
      (node (ref "U10F") (pin "C7") (pinfunction "MGTPTXN3_216_C7") (pintype "output"))
    )
    (net (code "146") (name "/PERC2_P") (class "Default")
      (node (ref "C37F") (pin "2") (pinfunction "2_2") (pintype "passive"))
      (node (ref "U10F") (pin "D7") (pinfunction "MGTPTXP3_216_D7") (pintype "output"))
    )
    (net (code "147") (name "/PERC3_N") (class "Default")
      (node (ref "C22F") (pin "2") (pinfunction "2_2") (pintype "passive"))
      (node (ref "U10F") (pin "A4") (pinfunction "MGTPTXN0_216_A4") (pintype "output"))
    )
    (net (code "148") (name "/PERC3_P") (class "Default")
      (node (ref "C20F") (pin "2") (pinfunction "2_2") (pintype "passive"))
      (node (ref "U10F") (pin "B4") (pinfunction "MGTPTXP0_216_B4") (pintype "output"))
    )
    (net (code "149") (name "/PERST#") (class "Default")
      (node (ref "U10F") (pin "E18") (pinfunction "IO_L15N_T2_DQS_16_E18") (pintype "bidirectional"))
    )
    (net (code "150") (name "/PET0_N") (class "Default")
      (node (ref "U10F") (pin "C11") (pinfunction "MGTPRXN1_216_C11") (pintype "input"))
    )
    (net (code "151") (name "/PET0_P") (class "Default")
      (node (ref "U10F") (pin "D11") (pinfunction "MGTPRXP1_216_D11") (pintype "input"))
    )
    (net (code "152") (name "/PET1_N") (class "Default")
      (node (ref "U10F") (pin "A10") (pinfunction "MGTPRXN2_216_A10") (pintype "input"))
    )
    (net (code "153") (name "/PET1_P") (class "Default")
      (node (ref "U10F") (pin "B10") (pinfunction "MGTPRXP2_216_B10") (pintype "input"))
    )
    (net (code "154") (name "/PET2_N") (class "Default")
      (node (ref "U10F") (pin "C9") (pinfunction "MGTPRXN3_216_C9") (pintype "input"))
    )
    (net (code "155") (name "/PET2_P") (class "Default")
      (node (ref "U10F") (pin "D9") (pinfunction "MGTPRXP3_216_D9") (pintype "input"))
    )
    (net (code "156") (name "/PET3_N") (class "Default")
      (node (ref "U10F") (pin "A8") (pinfunction "MGTPRXN0_216_A8") (pintype "input"))
    )
    (net (code "157") (name "/PET3_P") (class "Default")
      (node (ref "U10F") (pin "B8") (pinfunction "MGTPRXP0_216_B8") (pintype "input"))
    )
    (net (code "158") (name "/REFCLK_N") (class "Default")
      (node (ref "C23F") (pin "2") (pinfunction "2_2") (pintype "passive"))
    )
    (net (code "159") (name "/REFCLK_P") (class "Default")
      (node (ref "C21F") (pin "2") (pinfunction "2_2") (pintype "passive"))
    )
    (net (code "160") (name "/RX0_FORCEPLUG") (class "Default")
      (node (ref "U10F") (pin "N22") (pinfunction "IO_L15P_T2_DQS_15_N22") (pintype "bidirectional"))
    )
    (net (code "161") (name "/RX0_FORCEUNPLUG") (class "Default")
      (node (ref "U10F") (pin "M22") (pinfunction "IO_L15N_T2_DQS_ADV_B_15_M22") (pintype "bidirectional"))
    )
    (net (code "162") (name "/RX0_TMDS0_N") (class "Default")
      (node (ref "U10F") (pin "K21") (pinfunction "IO_L9P_T1_DQS_AD3P_15_K21") (pintype "bidirectional"))
    )
    (net (code "163") (name "/RX0_TMDS0_P") (class "Default")
      (node (ref "U10F") (pin "K22") (pinfunction "IO_L9N_T1_DQS_AD3N_15_K22") (pintype "bidirectional"))
    )
    (net (code "164") (name "/RX0_TMDS1_N") (class "Default")
      (node (ref "U10F") (pin "J20") (pinfunction "IO_L11P_T1_SRCC_15_J20") (pintype "bidirectional"))
    )
    (net (code "165") (name "/RX0_TMDS1_P") (class "Default")
      (node (ref "U10F") (pin "J21") (pinfunction "IO_L11N_T1_SRCC_15_J21") (pintype "bidirectional"))
    )
    (net (code "166") (name "/RX0_TMDS2_N") (class "Default")
      (node (ref "U10F") (pin "J22") (pinfunction "IO_L7P_T1_AD2P_15_J22") (pintype "bidirectional"))
    )
    (net (code "167") (name "/RX0_TMDS2_P") (class "Default")
      (node (ref "U10F") (pin "H22") (pinfunction "IO_L7N_T1_AD2N_15_H22") (pintype "bidirectional"))
    )
    (net (code "168") (name "/RX0_TMDS3_N") (class "Default")
      (node (ref "U10F") (pin "L19") (pinfunction "IO_L14P_T2_SRCC_15_L19") (pintype "bidirectional"))
    )
    (net (code "169") (name "/RX0_TMDS3_P") (class "Default")
      (node (ref "U10F") (pin "L20") (pinfunction "IO_L14N_T2_SRCC_15_L20") (pintype "bidirectional"))
    )
    (net (code "170") (name "/SMCLK") (class "Default")
      (node (ref "U10F") (pin "D19") (pinfunction "IO_L14N_T2_SRCC_16_D19") (pintype "bidirectional"))
    )
    (net (code "171") (name "/SMDAT") (class "Default")
      (node (ref "U10F") (pin "D20") (pinfunction "IO_L19P_T3_16_D20") (pintype "bidirectional"))
    )
    (net (code "172") (name "/SYSCLK") (class "Default")
      (node (ref "U10F") (pin "J19") (pinfunction "IO_L12P_T1_MRCC_15_J19") (pintype "bidirectional"))
      (node (ref "U11F") (pin "3") (pinfunction "OUT_3") (pintype "output"))
    )
    (net (code "173") (name "/TX0_TMDS0_N") (class "Default")
      (node (ref "U10F") (pin "W22") (pinfunction "IO_L7N_T1_D10_14_W22") (pintype "bidirectional"))
    )
    (net (code "174") (name "/TX0_TMDS0_P") (class "Default")
      (node (ref "U10F") (pin "W21") (pinfunction "IO_L7P_T1_D09_14_W21") (pintype "bidirectional"))
    )
    (net (code "175") (name "/TX0_TMDS1_N") (class "Default")
      (node (ref "U10F") (pin "V20") (pinfunction "IO_L11N_T1_SRCC_14_V20") (pintype "bidirectional"))
    )
    (net (code "176") (name "/TX0_TMDS1_P") (class "Default")
      (node (ref "U10F") (pin "U20") (pinfunction "IO_L11P_T1_SRCC_14_U20") (pintype "bidirectional"))
    )
    (net (code "177") (name "/TX0_TMDS2_N") (class "Default")
      (node (ref "U10F") (pin "U21") (pinfunction "IO_L4N_T0_D05_14_U21") (pintype "bidirectional"))
    )
    (net (code "178") (name "/TX0_TMDS2_P") (class "Default")
      (node (ref "U10F") (pin "T21") (pinfunction "IO_L4P_T0_D04_14_T21") (pintype "bidirectional"))
    )
    (net (code "179") (name "/TX0_TMDS3_N") (class "Default")
      (node (ref "U10F") (pin "W19") (pinfunction "IO_L12P_T1_MRCC_14_W19") (pintype "bidirectional"))
    )
    (net (code "180") (name "/TX0_TMDS3_P") (class "Default")
      (node (ref "U10F") (pin "W20") (pinfunction "IO_L12N_T1_MRCC_14_W20") (pintype "bidirectional"))
    )
    (net (code "181") (name "/TX1_CEC") (class "Default")
      (node (ref "U10F") (pin "P17") (pinfunction "IO_L21N_T3_DQS_A06_D22_14_P17") (pintype "bidirectional"))
    )
    (net (code "182") (name "/TX1_CLK_N") (class "Default")
      (node (ref "U10F") (pin "G21") (pinfunction "IO_L24P_T3_16_G21") (pintype "bidirectional"))
    )
    (net (code "183") (name "/TX1_CLK_P") (class "Default")
      (node (ref "U10F") (pin "G22") (pinfunction "IO_L24N_T3_16_G22") (pintype "bidirectional"))
    )
    (net (code "184") (name "/TX1_HPD_LL") (class "Default")
      (node (ref "U10F") (pin "U18") (pinfunction "IO_L18N_T2_A11_D27_14_U18") (pintype "bidirectional"))
    )
    (net (code "185") (name "/TX1_SCL_LV") (class "Default")
      (node (ref "U10F") (pin "P16") (pinfunction "IO_L24P_T3_A01_D17_14_P16") (pintype "bidirectional"))
    )
    (net (code "186") (name "/TX1_SDA_LV") (class "Default")
      (node (ref "U10F") (pin "R16") (pinfunction "IO_L22N_T3_A04_D20_14_R16") (pintype "bidirectional"))
    )
    (net (code "187") (name "/TX1_TMDS0_N") (class "Default")
      (node (ref "U10F") (pin "E22") (pinfunction "IO_L22P_T3_16_E22") (pintype "bidirectional"))
    )
    (net (code "188") (name "/TX1_TMDS0_P") (class "Default")
      (node (ref "U10F") (pin "D22") (pinfunction "IO_L22N_T3_16_D22") (pintype "bidirectional"))
    )
    (net (code "189") (name "/TX1_TMDS1_N") (class "Default")
      (node (ref "U10F") (pin "C22") (pinfunction "IO_L20P_T3_16_C22") (pintype "bidirectional"))
    )
    (net (code "190") (name "/TX1_TMDS1_P") (class "Default")
      (node (ref "U10F") (pin "B22") (pinfunction "IO_L20N_T3_16_B22") (pintype "bidirectional"))
    )
    (net (code "191") (name "/TX1_TMDS2_N") (class "Default")
      (node (ref "U10F") (pin "B21") (pinfunction "IO_L21P_T3_DQS_16_B21") (pintype "bidirectional"))
    )
    (net (code "192") (name "/TX1_TMDS2_P") (class "Default")
      (node (ref "U10F") (pin "A21") (pinfunction "IO_L21N_T3_DQS_16_A21") (pintype "bidirectional"))
    )
    (net (code "193") (name "/UART0_RX") (class "Default")
      (node (ref "U10F") (pin "E13") (pinfunction "IO_L4P_T0_16_E13") (pintype "bidirectional"))
    )
    (net (code "194") (name "/UART0_TX") (class "Default")
      (node (ref "U10F") (pin "E14") (pinfunction "IO_L4N_T0_16_E14") (pintype "bidirectional"))
    )
    (net (code "195") (name "/WAKE#") (class "Default")
      (node (ref "U10F") (pin "E19") (pinfunction "IO_L14P_T2_SRCC_16_E19") (pintype "bidirectional"))
    )
    (net (code "196") (name "GND") (class "Default")
      (node (ref "C10F") (pin "2") (pinfunction "2_2") (pintype "passive"))
      (node (ref "C11F") (pin "2") (pinfunction "2_2") (pintype "passive"))
      (node (ref "C12F") (pin "2") (pinfunction "2_2") (pintype "passive"))
      (node (ref "C13F") (pin "2") (pinfunction "2_2") (pintype "passive"))
      (node (ref "C14F") (pin "2") (pinfunction "2_2") (pintype "passive"))
      (node (ref "C15F") (pin "2") (pinfunction "2_2") (pintype "passive"))
      (node (ref "C16F") (pin "2") (pinfunction "2_2") (pintype "passive"))
      (node (ref "C17F") (pin "2") (pinfunction "2_2") (pintype "passive"))
      (node (ref "C18F") (pin "2") (pinfunction "2_2") (pintype "passive"))
      (node (ref "C19F") (pin "2") (pinfunction "2_2") (pintype "passive"))
      (node (ref "C26F") (pin "2") (pinfunction "2_2") (pintype "passive"))
      (node (ref "C28F") (pin "2") (pinfunction "2_2") (pintype "passive"))
      (node (ref "C29F") (pin "2") (pinfunction "2_2") (pintype "passive"))
      (node (ref "C30F") (pin "2") (pinfunction "2_2") (pintype "passive"))
      (node (ref "C31F") (pin "2") (pinfunction "2_2") (pintype "passive"))
      (node (ref "C32F") (pin "2") (pinfunction "2_2") (pintype "passive"))
      (node (ref "C33F") (pin "2") (pinfunction "2_2") (pintype "passive"))
      (node (ref "C34F") (pin "2") (pinfunction "2_2") (pintype "passive"))
      (node (ref "C35F") (pin "2") (pinfunction "2_2") (pintype "passive"))
      (node (ref "C38F") (pin "2") (pinfunction "2_2") (pintype "passive"))
      (node (ref "C39F") (pin "2") (pinfunction "2_2") (pintype "passive"))
      (node (ref "C41F") (pin "2") (pinfunction "2_2") (pintype "passive"))
      (node (ref "C42F") (pin "2") (pinfunction "2_2") (pintype "passive"))
      (node (ref "C43F") (pin "2") (pinfunction "2_2") (pintype "passive"))
      (node (ref "C44F") (pin "2") (pinfunction "2_2") (pintype "passive"))
      (node (ref "C45F") (pin "2") (pinfunction "2_2") (pintype "passive"))
      (node (ref "C46F") (pin "2") (pinfunction "2_2") (pintype "passive"))
      (node (ref "C47F") (pin "2") (pinfunction "2_2") (pintype "passive"))
      (node (ref "C48F") (pin "2") (pinfunction "2_2") (pintype "passive"))
      (node (ref "C49F") (pin "2") (pinfunction "2_2") (pintype "passive"))
      (node (ref "C50F") (pin "2") (pinfunction "2_2") (pintype "passive"))
      (node (ref "C51F") (pin "2") (pinfunction "2_2") (pintype "passive"))
      (node (ref "C52F") (pin "2") (pinfunction "2_2") (pintype "passive"))
      (node (ref "C53F") (pin "2") (pinfunction "2_2") (pintype "passive"))
      (node (ref "C54F") (pin "2") (pinfunction "2_2") (pintype "passive"))
      (node (ref "C55F") (pin "2") (pinfunction "2_2") (pintype "passive"))
      (node (ref "C56F") (pin "2") (pinfunction "2_2") (pintype "passive"))
      (node (ref "C57F") (pin "2") (pinfunction "2_2") (pintype "passive"))
      (node (ref "C58F") (pin "2") (pinfunction "2_2") (pintype "passive"))
      (node (ref "C59F") (pin "2") (pinfunction "2_2") (pintype "passive"))
      (node (ref "C60F") (pin "2") (pinfunction "2_2") (pintype "passive"))
      (node (ref "C61F") (pin "2") (pinfunction "2_2") (pintype "passive"))
      (node (ref "C62F") (pin "2") (pinfunction "2_2") (pintype "passive"))
      (node (ref "C63F") (pin "2") (pinfunction "2_2") (pintype "passive"))
      (node (ref "C64F") (pin "2") (pinfunction "2_2") (pintype "passive"))
      (node (ref "C65F") (pin "2") (pinfunction "2_2") (pintype "passive"))
      (node (ref "C66F") (pin "2") (pinfunction "2_2") (pintype "passive"))
      (node (ref "C67F") (pin "2") (pinfunction "2_2") (pintype "passive"))
      (node (ref "C68F") (pin "2") (pinfunction "2_2") (pintype "passive"))
      (node (ref "C69F") (pin "2") (pinfunction "2_2") (pintype "passive"))
      (node (ref "C70F") (pin "2") (pinfunction "2_2") (pintype "passive"))
      (node (ref "C71F") (pin "2") (pinfunction "2_2") (pintype "passive"))
      (node (ref "C72F") (pin "2") (pinfunction "2_2") (pintype "passive"))
      (node (ref "C73F") (pin "2") (pinfunction "2_2") (pintype "passive"))
      (node (ref "C74F") (pin "2") (pinfunction "2_2") (pintype "passive"))
      (node (ref "C75F") (pin "2") (pinfunction "2_2") (pintype "passive"))
      (node (ref "C76F") (pin "2") (pinfunction "2_2") (pintype "passive"))
      (node (ref "C77F") (pin "2") (pinfunction "2_2") (pintype "passive"))
      (node (ref "C78F") (pin "2") (pinfunction "2_2") (pintype "passive"))
      (node (ref "C79F") (pin "2") (pinfunction "2_2") (pintype "passive"))
      (node (ref "C80F") (pin "2") (pinfunction "2_2") (pintype "passive"))
      (node (ref "C81F") (pin "2") (pinfunction "2_2") (pintype "passive"))
      (node (ref "C82F") (pin "2") (pinfunction "2_2") (pintype "passive"))
      (node (ref "C83F") (pin "2") (pinfunction "2_2") (pintype "passive"))
      (node (ref "C84F") (pin "2") (pinfunction "2_2") (pintype "passive"))
      (node (ref "C85F") (pin "2") (pinfunction "2_2") (pintype "passive"))
      (node (ref "C86F") (pin "2") (pinfunction "2_2") (pintype "passive"))
      (node (ref "C87F") (pin "2") (pinfunction "2_2") (pintype "passive"))
      (node (ref "C88F") (pin "2") (pinfunction "2_2") (pintype "passive"))
      (node (ref "C89F") (pin "2") (pinfunction "2_2") (pintype "passive"))
      (node (ref "D10F") (pin "2") (pinfunction "K_2") (pintype "passive"))
      (node (ref "D11F") (pin "2") (pinfunction "K_2") (pintype "passive"))
      (node (ref "D12F") (pin "2") (pinfunction "K_2") (pintype "passive"))
      (node (ref "R10F") (pin "2") (pinfunction "2_2") (pintype "passive"))
      (node (ref "R15F") (pin "1") (pinfunction "1_1") (pintype "passive"))
      (node (ref "U10F") (pin "A11") (pinfunction "GND_A11") (pintype "power_in"))
      (node (ref "U10F") (pin "A12") (pinfunction "GND_A12") (pintype "power_in"))
      (node (ref "U10F") (pin "A2") (pinfunction "GND_A2") (pintype "power_in"))
      (node (ref "U10F") (pin "A22") (pinfunction "GND_A22") (pintype "power_in"))
      (node (ref "U10F") (pin "A3") (pinfunction "GND_A3") (pintype "power_in"))
      (node (ref "U10F") (pin "A5") (pinfunction "GND_A5") (pintype "power_in"))
      (node (ref "U10F") (pin "A7") (pinfunction "GND_A7") (pintype "power_in"))
      (node (ref "U10F") (pin "A9") (pinfunction "GND_A9") (pintype "power_in"))
      (node (ref "U10F") (pin "AA12") (pinfunction "GND_AA12") (pintype "power_in"))
      (node (ref "U10F") (pin "AA2") (pinfunction "GND_AA2") (pintype "power_in"))
      (node (ref "U10F") (pin "AA22") (pinfunction "GND_AA22") (pintype "power_in"))
      (node (ref "U10F") (pin "AB19") (pinfunction "GND_AB19") (pintype "power_in"))
      (node (ref "U10F") (pin "AB9") (pinfunction "GND_AB9") (pintype "power_in"))
      (node (ref "U10F") (pin "B12") (pinfunction "GND_B12") (pintype "power_in"))
      (node (ref "U10F") (pin "B19") (pinfunction "GND_B19") (pintype "power_in"))
      (node (ref "U10F") (pin "B3") (pinfunction "GND_B3") (pintype "power_in"))
      (node (ref "U10F") (pin "C10") (pinfunction "GND_C10") (pintype "power_in"))
      (node (ref "U10F") (pin "C12") (pinfunction "GND_C12") (pintype "power_in"))
      (node (ref "U10F") (pin "C16") (pinfunction "GND_C16") (pintype "power_in"))
      (node (ref "U10F") (pin "C3") (pinfunction "GND_C3") (pintype "power_in"))
      (node (ref "U10F") (pin "C6") (pinfunction "GND_C6") (pintype "power_in"))
      (node (ref "U10F") (pin "D12") (pinfunction "GND_D12") (pintype "power_in"))
      (node (ref "U10F") (pin "D13") (pinfunction "GND_D13") (pintype "power_in"))
      (node (ref "U10F") (pin "D3") (pinfunction "GND_D3") (pintype "power_in"))
      (node (ref "U10F") (pin "D4") (pinfunction "GND_D4") (pintype "power_in"))
      (node (ref "U10F") (pin "D8") (pinfunction "GND_D8") (pintype "power_in"))
      (node (ref "U10F") (pin "E11") (pinfunction "GND_E11") (pintype "power_in"))
      (node (ref "U10F") (pin "E20") (pinfunction "GND_E20") (pintype "power_in"))
      (node (ref "U10F") (pin "E4") (pinfunction "GND_E4") (pintype "power_in"))
      (node (ref "U10F") (pin "E5") (pinfunction "GND_E5") (pintype "power_in"))
      (node (ref "U10F") (pin "E7") (pinfunction "GND_E7") (pintype "power_in"))
      (node (ref "U10F") (pin "E9") (pinfunction "GND_E9") (pintype "power_in"))
      (node (ref "U10F") (pin "F11") (pinfunction "GND_F11") (pintype "power_in"))
      (node (ref "U10F") (pin "F17") (pinfunction "GND_F17") (pintype "power_in"))
      (node (ref "U10F") (pin "F5") (pinfunction "GND_F5") (pintype "power_in"))
      (node (ref "U10F") (pin "G10") (pinfunction "GND_G10") (pintype "power_in"))
      (node (ref "U10F") (pin "G12") (pinfunction "GND_G12") (pintype "power_in"))
      (node (ref "U10F") (pin "G14") (pinfunction "GND_G14") (pintype "power_in"))
      (node (ref "U10F") (pin "G5") (pinfunction "GND_G5") (pintype "power_in"))
      (node (ref "U10F") (pin "G6") (pinfunction "GND_G6") (pintype "power_in"))
      (node (ref "U10F") (pin "G7") (pinfunction "GND_G7") (pintype "power_in"))
      (node (ref "U10F") (pin "G8") (pinfunction "GND_G8") (pintype "power_in"))
      (node (ref "U10F") (pin "G9") (pinfunction "GND_G9") (pintype "power_in"))
      (node (ref "U10F") (pin "H1") (pinfunction "GND_H1") (pintype "power_in"))
      (node (ref "U10F") (pin "H11") (pinfunction "GND_H11") (pintype "power_in"))
      (node (ref "U10F") (pin "H21") (pinfunction "GND_H21") (pintype "power_in"))
      (node (ref "U10F") (pin "H7") (pinfunction "GND_H7") (pintype "power_in"))
      (node (ref "U10F") (pin "H9") (pinfunction "GND_H9") (pintype "power_in"))
      (node (ref "U10F") (pin "J10") (pinfunction "GND_J10") (pintype "power_in"))
      (node (ref "U10F") (pin "J12") (pinfunction "GND_J12") (pintype "power_in"))
      (node (ref "U10F") (pin "J18") (pinfunction "GND_J18") (pintype "power_in"))
      (node (ref "U10F") (pin "J8") (pinfunction "GND_J8") (pintype "power_in"))
      (node (ref "U10F") (pin "K11") (pinfunction "GND_K11") (pintype "power_in"))
      (node (ref "U10F") (pin "K15") (pinfunction "GND_K15") (pintype "power_in"))
      (node (ref "U10F") (pin "K5") (pinfunction "GND_K5") (pintype "power_in"))
      (node (ref "U10F") (pin "K7") (pinfunction "GND_K7") (pintype "power_in"))
      (node (ref "U10F") (pin "K9") (pinfunction "GNDADC_0_K9") (pintype "power_in"))
      (node (ref "U10F") (pin "L10") (pinfunction "VP_0_L10") (pintype "input"))
      (node (ref "U10F") (pin "L2") (pinfunction "GND_L2") (pintype "power_in"))
      (node (ref "U10F") (pin "L22") (pinfunction "GND_L22") (pintype "power_in"))
      (node (ref "U10F") (pin "L8") (pinfunction "GND_L8") (pintype "power_in"))
      (node (ref "U10F") (pin "L9") (pinfunction "VREFN_0_L9") (pintype "input"))
      (node (ref "U10F") (pin "M10") (pinfunction "VREFP_0_M10") (pintype "input"))
      (node (ref "U10F") (pin "M11") (pinfunction "GND_M11") (pintype "power_in"))
      (node (ref "U10F") (pin "M19") (pinfunction "GND_M19") (pintype "power_in"))
      (node (ref "U10F") (pin "M7") (pinfunction "GND_M7") (pintype "power_in"))
      (node (ref "U10F") (pin "M9") (pinfunction "VN_0_M9") (pintype "input"))
      (node (ref "U10F") (pin "N10") (pinfunction "DXP_0_N10") (pintype "input"))
      (node (ref "U10F") (pin "N16") (pinfunction "GND_N16") (pintype "power_in"))
      (node (ref "U10F") (pin "N6") (pinfunction "GND_N6") (pintype "power_in"))
      (node (ref "U10F") (pin "N8") (pinfunction "GND_N8") (pintype "power_in"))
      (node (ref "U10F") (pin "N9") (pinfunction "DXN_0_N9") (pintype "input"))
      (node (ref "U10F") (pin "P11") (pinfunction "GND_P11") (pintype "power_in"))
      (node (ref "U10F") (pin "P13") (pinfunction "GND_P13") (pintype "power_in"))
      (node (ref "U10F") (pin "P3") (pinfunction "GND_P3") (pintype "power_in"))
      (node (ref "U10F") (pin "P7") (pinfunction "GND_P7") (pintype "power_in"))
      (node (ref "U10F") (pin "P9") (pinfunction "GND_P9") (pintype "power_in"))
      (node (ref "U10F") (pin "R10") (pinfunction "GND_R10") (pintype "power_in"))
      (node (ref "U10F") (pin "R12") (pinfunction "GND_R12") (pintype "power_in"))
      (node (ref "U10F") (pin "R20") (pinfunction "GND_R20") (pintype "power_in"))
      (node (ref "U10F") (pin "R8") (pinfunction "GND_R8") (pintype "power_in"))
      (node (ref "U10F") (pin "T11") (pinfunction "GND_T11") (pintype "power_in"))
      (node (ref "U10F") (pin "T17") (pinfunction "GND_T17") (pintype "power_in"))
      (node (ref "U10F") (pin "T7") (pinfunction "GND_T7") (pintype "power_in"))
      (node (ref "U10F") (pin "T9") (pinfunction "GND_T9") (pintype "power_in"))
      (node (ref "U10F") (pin "U10") (pinfunction "M1_0_U10") (pintype "input"))
      (node (ref "U10F") (pin "U14") (pinfunction "GND_U14") (pintype "power_in"))
      (node (ref "U10F") (pin "U4") (pinfunction "GND_U4") (pintype "power_in"))
      (node (ref "U10F") (pin "V1") (pinfunction "GND_V1") (pintype "power_in"))
      (node (ref "U10F") (pin "V11") (pinfunction "GND_V11") (pintype "power_in"))
      (node (ref "U10F") (pin "V21") (pinfunction "GND_V21") (pintype "power_in"))
      (node (ref "U10F") (pin "W18") (pinfunction "GND_W18") (pintype "power_in"))
      (node (ref "U10F") (pin "W8") (pinfunction "GND_W8") (pintype "power_in"))
      (node (ref "U10F") (pin "Y15") (pinfunction "GND_Y15") (pintype "power_in"))
      (node (ref "U10F") (pin "Y5") (pinfunction "GND_Y5") (pintype "power_in"))
      (node (ref "U11F") (pin "2") (pinfunction "GND_2") (pintype "power_in"))
    )
    (net (code "197") (name "Net-(D10F-A)") (class "Default")
      (node (ref "D10F") (pin "1") (pinfunction "A_1") (pintype "passive"))
      (node (ref "R16F") (pin "1") (pinfunction "1_1") (pintype "passive"))
    )
    (net (code "198") (name "Net-(D11F-A)") (class "Default")
      (node (ref "D11F") (pin "1") (pinfunction "A_1") (pintype "passive"))
      (node (ref "R17F") (pin "1") (pinfunction "1_1") (pintype "passive"))
    )
    (net (code "199") (name "Net-(D12F-A)") (class "Default")
      (node (ref "D12F") (pin "1") (pinfunction "A_1") (pintype "passive"))
      (node (ref "R18F") (pin "1") (pinfunction "1_1") (pintype "passive"))
    )
    (net (code "200") (name "Net-(U10FG-MGTRREF_216)") (class "Default")
      (node (ref "R11F") (pin "1") (pinfunction "1_1") (pintype "passive"))
      (node (ref "U10F") (pin "F8") (pinfunction "MGTRREF_216_F8") (pintype "input"))
    )
    (net (code "201") (name "P1.0V") (class "Default")
      (node (ref "C10F") (pin "1") (pinfunction "1_1") (pintype "passive"))
      (node (ref "C11F") (pin "1") (pinfunction "1_1") (pintype "passive"))
      (node (ref "C12F") (pin "1") (pinfunction "1_1") (pintype "passive"))
      (node (ref "C38F") (pin "1") (pinfunction "1_1") (pintype "passive"))
      (node (ref "C39F") (pin "1") (pinfunction "1_1") (pintype "passive"))
      (node (ref "C41F") (pin "1") (pinfunction "1_1") (pintype "passive"))
      (node (ref "C42F") (pin "1") (pinfunction "1_1") (pintype "passive"))
      (node (ref "C43F") (pin "1") (pinfunction "1_1") (pintype "passive"))
      (node (ref "C44F") (pin "1") (pinfunction "1_1") (pintype "passive"))
      (node (ref "C45F") (pin "1") (pinfunction "1_1") (pintype "passive"))
      (node (ref "C46F") (pin "1") (pinfunction "1_1") (pintype "passive"))
      (node (ref "C47F") (pin "1") (pinfunction "1_1") (pintype "passive"))
      (node (ref "C48F") (pin "1") (pinfunction "1_1") (pintype "passive"))
      (node (ref "C49F") (pin "1") (pinfunction "1_1") (pintype "passive"))
      (node (ref "U10F") (pin "D10") (pinfunction "MGTAVCC_D10") (pintype "power_in"))
      (node (ref "U10F") (pin "D6") (pinfunction "MGTAVCC_D6") (pintype "power_in"))
      (node (ref "U10F") (pin "E8") (pinfunction "MGTAVCC_E8") (pintype "power_in"))
      (node (ref "U10F") (pin "F7") (pinfunction "MGTAVCC_F7") (pintype "power_in"))
      (node (ref "U10F") (pin "F9") (pinfunction "MGTAVCC_F9") (pintype "power_in"))
      (node (ref "U10F") (pin "H10") (pinfunction "VCCINT_H10") (pintype "power_in"))
      (node (ref "U10F") (pin "H8") (pinfunction "VCCINT_H8") (pintype "power_in"))
      (node (ref "U10F") (pin "J11") (pinfunction "VCCBRAM_J11") (pintype "power_in"))
      (node (ref "U10F") (pin "J7") (pinfunction "VCCINT_J7") (pintype "power_in"))
      (node (ref "U10F") (pin "J9") (pinfunction "VCCINT_J9") (pintype "power_in"))
      (node (ref "U10F") (pin "K8") (pinfunction "VCCINT_K8") (pintype "power_in"))
      (node (ref "U10F") (pin "L11") (pinfunction "VCCBRAM_L11") (pintype "power_in"))
      (node (ref "U10F") (pin "L7") (pinfunction "VCCINT_L7") (pintype "power_in"))
      (node (ref "U10F") (pin "M8") (pinfunction "VCCINT_M8") (pintype "power_in"))
      (node (ref "U10F") (pin "N11") (pinfunction "VCCBRAM_N11") (pintype "power_in"))
      (node (ref "U10F") (pin "N7") (pinfunction "VCCINT_N7") (pintype "power_in"))
      (node (ref "U10F") (pin "P10") (pinfunction "VCCINT_P10") (pintype "power_in"))
      (node (ref "U10F") (pin "P8") (pinfunction "VCCINT_P8") (pintype "power_in"))
      (node (ref "U10F") (pin "R7") (pinfunction "VCCINT_R7") (pintype "power_in"))
      (node (ref "U10F") (pin "R9") (pinfunction "VCCINT_R9") (pintype "power_in"))
      (node (ref "U10F") (pin "T10") (pinfunction "VCCINT_T10") (pintype "power_in"))
      (node (ref "U10F") (pin "T8") (pinfunction "VCCINT_T8") (pintype "power_in"))
    )
    (net (code "202") (name "P1.2VTT") (class "Default")
      (node (ref "C15F") (pin "1") (pinfunction "1_1") (pintype "passive"))
      (node (ref "C16F") (pin "1") (pinfunction "1_1") (pintype "passive"))
      (node (ref "C17F") (pin "1") (pinfunction "1_1") (pintype "passive"))
      (node (ref "C87F") (pin "1") (pinfunction "1_1") (pintype "passive"))
      (node (ref "C88F") (pin "1") (pinfunction "1_1") (pintype "passive"))
      (node (ref "R11F") (pin "2") (pinfunction "2_2") (pintype "passive"))
      (node (ref "U10F") (pin "B11") (pinfunction "MGTAVTT_B11") (pintype "power_in"))
      (node (ref "U10F") (pin "B5") (pinfunction "MGTAVTT_B5") (pintype "power_in"))
      (node (ref "U10F") (pin "B7") (pinfunction "MGTAVTT_B7") (pintype "power_in"))
      (node (ref "U10F") (pin "B9") (pinfunction "MGTAVTT_B9") (pintype "power_in"))
      (node (ref "U10F") (pin "C4") (pinfunction "MGTAVTT_C4") (pintype "power_in"))
      (node (ref "U10F") (pin "C8") (pinfunction "MGTAVTT_C8") (pintype "power_in"))
    )
    (net (code "203") (name "P1.5V_D") (class "Default")
      (node (ref "C59F") (pin "1") (pinfunction "1_1") (pintype "passive"))
      (node (ref "C60F") (pin "1") (pinfunction "1_1") (pintype "passive"))
      (node (ref "C61F") (pin "1") (pinfunction "1_1") (pintype "passive"))
      (node (ref "C62F") (pin "1") (pinfunction "1_1") (pintype "passive"))
      (node (ref "C63F") (pin "1") (pinfunction "1_1") (pintype "passive"))
      (node (ref "C64F") (pin "1") (pinfunction "1_1") (pintype "passive"))
      (node (ref "C65F") (pin "1") (pinfunction "1_1") (pintype "passive"))
      (node (ref "C73F") (pin "1") (pinfunction "1_1") (pintype "passive"))
      (node (ref "C74F") (pin "1") (pinfunction "1_1") (pintype "passive"))
      (node (ref "C75F") (pin "1") (pinfunction "1_1") (pintype "passive"))
      (node (ref "C76F") (pin "1") (pinfunction "1_1") (pintype "passive"))
      (node (ref "C77F") (pin "1") (pinfunction "1_1") (pintype "passive"))
      (node (ref "C78F") (pin "1") (pinfunction "1_1") (pintype "passive"))
      (node (ref "C79F") (pin "1") (pinfunction "1_1") (pintype "passive"))
      (node (ref "U10F") (pin "AA7") (pinfunction "VCCO_34_AA7") (pintype "power_in"))
      (node (ref "U10F") (pin "AB4") (pinfunction "VCCO_34_AB4") (pintype "power_in"))
      (node (ref "U10F") (pin "C1") (pinfunction "VCCO_35_C1") (pintype "power_in"))
      (node (ref "U10F") (pin "F2") (pinfunction "VCCO_35_F2") (pintype "power_in"))
      (node (ref "U10F") (pin "H6") (pinfunction "VCCO_35_H6") (pintype "power_in"))
      (node (ref "U10F") (pin "J3") (pinfunction "VCCO_35_J3") (pintype "power_in"))
      (node (ref "U10F") (pin "M4") (pinfunction "VCCO_35_M4") (pintype "power_in"))
      (node (ref "U10F") (pin "N1") (pinfunction "VCCO_35_N1") (pintype "power_in"))
      (node (ref "U10F") (pin "R5") (pinfunction "VCCO_34_R5") (pintype "power_in"))
      (node (ref "U10F") (pin "T2") (pinfunction "VCCO_34_T2") (pintype "power_in"))
      (node (ref "U10F") (pin "V6") (pinfunction "VCCO_34_V6") (pintype "power_in"))
      (node (ref "U10F") (pin "W3") (pinfunction "VCCO_34_W3") (pintype "power_in"))
    )
    (net (code "204") (name "P1.8V") (class "Default")
      (node (ref "C26F") (pin "1") (pinfunction "1_1") (pintype "passive"))
      (node (ref "C28F") (pin "1") (pinfunction "1_1") (pintype "passive"))
      (node (ref "C29F") (pin "1") (pinfunction "1_1") (pintype "passive"))
      (node (ref "C30F") (pin "1") (pinfunction "1_1") (pintype "passive"))
      (node (ref "C31F") (pin "1") (pinfunction "1_1") (pintype "passive"))
      (node (ref "C32F") (pin "1") (pinfunction "1_1") (pintype "passive"))
      (node (ref "C33F") (pin "1") (pinfunction "1_1") (pintype "passive"))
      (node (ref "C34F") (pin "1") (pinfunction "1_1") (pintype "passive"))
      (node (ref "C35F") (pin "1") (pinfunction "1_1") (pintype "passive"))
      (node (ref "U10F") (pin "E12") (pinfunction "VCCBATT_0_E12") (pintype "power_in"))
      (node (ref "U10F") (pin "H12") (pinfunction "VCCAUX_H12") (pintype "power_in"))
      (node (ref "U10F") (pin "K10") (pinfunction "VCCADC_0_K10") (pintype "power_in"))
      (node (ref "U10F") (pin "K12") (pinfunction "VCCAUX_K12") (pintype "power_in"))
      (node (ref "U10F") (pin "M12") (pinfunction "VCCAUX_M12") (pintype "power_in"))
      (node (ref "U10F") (pin "P12") (pinfunction "VCCAUX_P12") (pintype "power_in"))
      (node (ref "U10F") (pin "R11") (pinfunction "VCCAUX_R11") (pintype "power_in"))
    )
    (net (code "205") (name "P3.3V") (class "Default")
      (node (ref "C50F") (pin "1") (pinfunction "1_1") (pintype "passive"))
      (node (ref "C51F") (pin "1") (pinfunction "1_1") (pintype "passive"))
      (node (ref "C52F") (pin "1") (pinfunction "1_1") (pintype "passive"))
      (node (ref "C53F") (pin "1") (pinfunction "1_1") (pintype "passive"))
      (node (ref "C54F") (pin "1") (pinfunction "1_1") (pintype "passive"))
      (node (ref "C55F") (pin "1") (pinfunction "1_1") (pintype "passive"))
      (node (ref "C56F") (pin "1") (pinfunction "1_1") (pintype "passive"))
      (node (ref "C57F") (pin "1") (pinfunction "1_1") (pintype "passive"))
      (node (ref "C58F") (pin "1") (pinfunction "1_1") (pintype "passive"))
      (node (ref "C66F") (pin "1") (pinfunction "1_1") (pintype "passive"))
      (node (ref "C67F") (pin "1") (pinfunction "1_1") (pintype "passive"))
      (node (ref "C68F") (pin "1") (pinfunction "1_1") (pintype "passive"))
      (node (ref "C69F") (pin "1") (pinfunction "1_1") (pintype "passive"))
      (node (ref "C70F") (pin "1") (pinfunction "1_1") (pintype "passive"))
      (node (ref "C71F") (pin "1") (pinfunction "1_1") (pintype "passive"))
      (node (ref "C72F") (pin "1") (pinfunction "1_1") (pintype "passive"))
      (node (ref "C80F") (pin "1") (pinfunction "1_1") (pintype "passive"))
      (node (ref "C81F") (pin "1") (pinfunction "1_1") (pintype "passive"))
      (node (ref "C82F") (pin "1") (pinfunction "1_1") (pintype "passive"))
      (node (ref "C83F") (pin "1") (pinfunction "1_1") (pintype "passive"))
      (node (ref "C84F") (pin "1") (pinfunction "1_1") (pintype "passive"))
      (node (ref "C85F") (pin "1") (pinfunction "1_1") (pintype "passive"))
      (node (ref "C86F") (pin "1") (pinfunction "1_1") (pintype "passive"))
      (node (ref "C89F") (pin "1") (pinfunction "1_1") (pintype "passive"))
      (node (ref "P10F") (pin "2") (pinfunction "2_2") (pintype "passive"))
      (node (ref "R12F") (pin "2") (pinfunction "2_2") (pintype "passive"))
      (node (ref "R13F") (pin "2") (pinfunction "2_2") (pintype "passive"))
      (node (ref "R14F") (pin "2") (pinfunction "2_2") (pintype "passive"))
      (node (ref "U10F") (pin "A17") (pinfunction "VCCO_16_A17") (pintype "power_in"))
      (node (ref "U10F") (pin "AA17") (pinfunction "VCCO_13_AA17") (pintype "power_in"))
      (node (ref "U10F") (pin "AB14") (pinfunction "VCCO_13_AB14") (pintype "power_in"))
      (node (ref "U10F") (pin "B14") (pinfunction "VCCO_16_B14") (pintype "power_in"))
      (node (ref "U10F") (pin "C21") (pinfunction "VCCO_16_C21") (pintype "power_in"))
      (node (ref "U10F") (pin "D18") (pinfunction "VCCO_16_D18") (pintype "power_in"))
      (node (ref "U10F") (pin "E15") (pinfunction "VCCO_16_E15") (pintype "power_in"))
      (node (ref "U10F") (pin "F12") (pinfunction "VCCO_0_F12") (pintype "power_in"))
      (node (ref "U10F") (pin "F22") (pinfunction "VCCO_16_F22") (pintype "power_in"))
      (node (ref "U10F") (pin "G19") (pinfunction "VCCO_15_G19") (pintype "power_in"))
      (node (ref "U10F") (pin "H16") (pinfunction "VCCO_15_H16") (pintype "power_in"))
      (node (ref "U10F") (pin "J13") (pinfunction "VCCO_15_J13") (pintype "power_in"))
      (node (ref "U10F") (pin "K20") (pinfunction "VCCO_15_K20") (pintype "power_in"))
      (node (ref "U10F") (pin "L17") (pinfunction "VCCO_15_L17") (pintype "power_in"))
      (node (ref "U10F") (pin "M14") (pinfunction "VCCO_14_M14") (pintype "power_in"))
      (node (ref "U10F") (pin "N21") (pinfunction "VCCO_15_N21") (pintype "power_in"))
      (node (ref "U10F") (pin "P18") (pinfunction "VCCO_14_P18") (pintype "power_in"))
      (node (ref "U10F") (pin "R15") (pinfunction "VCCO_14_R15") (pintype "power_in"))
      (node (ref "U10F") (pin "T12") (pinfunction "VCCO_0_T12") (pintype "power_in"))
      (node (ref "U10F") (pin "T22") (pinfunction "VCCO_14_T22") (pintype "power_in"))
      (node (ref "U10F") (pin "U11") (pinfunction "M0_0_U11") (pintype "input"))
      (node (ref "U10F") (pin "U19") (pinfunction "VCCO_14_U19") (pintype "power_in"))
      (node (ref "U10F") (pin "U8") (pinfunction "CFGBVS_0_U8") (pintype "input"))
      (node (ref "U10F") (pin "V16") (pinfunction "VCCO_13_V16") (pintype "power_in"))
      (node (ref "U10F") (pin "W13") (pinfunction "VCCO_13_W13") (pintype "power_in"))
      (node (ref "U10F") (pin "Y10") (pinfunction "VCCO_13_Y10") (pintype "power_in"))
      (node (ref "U10F") (pin "Y20") (pinfunction "VCCO_14_Y20") (pintype "power_in"))
      (node (ref "U11F") (pin "1") (pinfunction "OE_1") (pintype "passive"))
      (node (ref "U11F") (pin "4") (pinfunction "Vcc_4") (pintype "power_in"))
    )
    (net (code "206") (name "VTT_REF") (class "Default")
      (node (ref "C13F") (pin "1") (pinfunction "1_1") (pintype "passive"))
      (node (ref "C14F") (pin "1") (pinfunction "1_1") (pintype "passive"))
      (node (ref "C18F") (pin "1") (pinfunction "1_1") (pintype "passive"))
      (node (ref "C19F") (pin "1") (pinfunction "1_1") (pintype "passive"))
      (node (ref "U10F") (pin "E3") (pinfunction "IO_L6N_T0_VREF_35_E3") (pintype "bidirectional"))
      (node (ref "U10F") (pin "N3") (pinfunction "IO_L19N_T3_VREF_35_N3") (pintype "bidirectional"))
      (node (ref "U10F") (pin "V3") (pinfunction "IO_L6N_T0_VREF_34_V3") (pintype "bidirectional"))
      (node (ref "U10F") (pin "W7") (pinfunction "IO_L19N_T3_VREF_34_W7") (pintype "bidirectional"))
    )
    (net (code "207") (name "unconnected-(U10FA-IO_25_14-PadN15)") (class "Default")
      (node (ref "U10F") (pin "N15") (pinfunction "IO_25_14_N15") (pintype "bidirectional"))
    )
    (net (code "208") (name "unconnected-(U10FA-IO_L3N_T0_DQS_EMCCLK_14-PadV22)") (class "Default")
      (node (ref "U10F") (pin "V22") (pinfunction "IO_L3N_T0_DQS_EMCCLK_14_V22") (pintype "bidirectional"))
    )
    (net (code "209") (name "unconnected-(U10FA-IO_L5N_T0_D07_14-PadR19)") (class "Default")
      (node (ref "U10F") (pin "R19") (pinfunction "IO_L5N_T0_D07_14_R19") (pintype "bidirectional"))
    )
    (net (code "210") (name "unconnected-(U10FA-IO_L6N_T0_D08_VREF_14-PadT20)") (class "Default")
      (node (ref "U10F") (pin "T20") (pinfunction "IO_L6N_T0_D08_VREF_14_T20") (pintype "bidirectional"))
    )
    (net (code "211") (name "unconnected-(U10FA-IO_L8N_T1_D12_14-PadAA21)") (class "Default")
      (node (ref "U10F") (pin "AA21") (pinfunction "IO_L8N_T1_D12_14_AA21") (pintype "bidirectional"))
    )
    (net (code "212") (name "unconnected-(U10FA-IO_L8P_T1_D11_14-PadAA20)") (class "Default")
      (node (ref "U10F") (pin "AA20") (pinfunction "IO_L8P_T1_D11_14_AA20") (pintype "bidirectional"))
    )
    (net (code "213") (name "unconnected-(U10FA-IO_L9N_T1_DQS_D13_14-PadY22)") (class "Default")
      (node (ref "U10F") (pin "Y22") (pinfunction "IO_L9N_T1_DQS_D13_14_Y22") (pintype "bidirectional"))
    )
    (net (code "214") (name "unconnected-(U10FA-IO_L9P_T1_DQS_14-PadY21)") (class "Default")
      (node (ref "U10F") (pin "Y21") (pinfunction "IO_L9P_T1_DQS_14_Y21") (pintype "bidirectional"))
    )
    (net (code "215") (name "unconnected-(U10FA-IO_L14N_T2_SRCC_14-PadV19)") (class "Default")
      (node (ref "U10F") (pin "V19") (pinfunction "IO_L14N_T2_SRCC_14_V19") (pintype "bidirectional"))
    )
    (net (code "216") (name "unconnected-(U10FA-IO_L19N_T3_A09_D25_VREF_14-PadR14)") (class "Default")
      (node (ref "U10F") (pin "R14") (pinfunction "IO_L19N_T3_A09_D25_VREF_14_R14") (pintype "bidirectional"))
    )
    (net (code "217") (name "unconnected-(U10FA-IO_L19P_T3_A10_D26_14-PadP14)") (class "Default")
      (node (ref "U10F") (pin "P14") (pinfunction "IO_L19P_T3_A10_D26_14_P14") (pintype "bidirectional"))
    )
    (net (code "218") (name "unconnected-(U10FA-IO_L20P_T3_A08_D24_14-PadR18)") (class "Default")
      (node (ref "U10F") (pin "R18") (pinfunction "IO_L20P_T3_A08_D24_14_R18") (pintype "bidirectional"))
    )
    (net (code "219") (name "unconnected-(U10FA-IO_L21P_T3_DQS_14-PadN17)") (class "Default")
      (node (ref "U10F") (pin "N17") (pinfunction "IO_L21P_T3_DQS_14_N17") (pintype "bidirectional"))
    )
    (net (code "220") (name "unconnected-(U10FA-IO_L22P_T3_A05_D21_14-PadP15)") (class "Default")
      (node (ref "U10F") (pin "P15") (pinfunction "IO_L22P_T3_A05_D21_14_P15") (pintype "bidirectional"))
    )
    (net (code "221") (name "unconnected-(U10FA-IO_L23N_T3_A02_D18_14-PadN14)") (class "Default")
      (node (ref "U10F") (pin "N14") (pinfunction "IO_L23N_T3_A02_D18_14_N14") (pintype "bidirectional"))
    )
    (net (code "222") (name "unconnected-(U10FA-IO_L23P_T3_A03_D19_14-PadN13)") (class "Default")
      (node (ref "U10F") (pin "N13") (pinfunction "IO_L23P_T3_A03_D19_14_N13") (pintype "bidirectional"))
    )
    (net (code "223") (name "unconnected-(U10FB-IO_0_15-PadJ16)") (class "Default")
      (node (ref "U10F") (pin "J16") (pinfunction "IO_0_15_J16") (pintype "bidirectional"))
    )
    (net (code "224") (name "unconnected-(U10FB-IO_25_15-PadM17)") (class "Default")
      (node (ref "U10F") (pin "M17") (pinfunction "IO_25_15_M17") (pintype "bidirectional"))
    )
    (net (code "225") (name "unconnected-(U10FB-IO_L1P_T0_AD0P_15-PadH13)") (class "Default")
      (node (ref "U10F") (pin "H13") (pinfunction "IO_L1P_T0_AD0P_15_H13") (pintype "bidirectional"))
    )
    (net (code "226") (name "unconnected-(U10FB-IO_L2N_T0_AD8N_15-PadG16)") (class "Default")
      (node (ref "U10F") (pin "G16") (pinfunction "IO_L2N_T0_AD8N_15_G16") (pintype "bidirectional"))
    )
    (net (code "227") (name "unconnected-(U10FB-IO_L2P_T0_AD8P_15-PadG15)") (class "Default")
      (node (ref "U10F") (pin "G15") (pinfunction "IO_L2P_T0_AD8P_15_G15") (pintype "bidirectional"))
    )
    (net (code "228") (name "unconnected-(U10FB-IO_L3N_T0_DQS_AD1N_15-PadH14)") (class "Default")
      (node (ref "U10F") (pin "H14") (pinfunction "IO_L3N_T0_DQS_AD1N_15_H14") (pintype "bidirectional"))
    )
    (net (code "229") (name "unconnected-(U10FB-IO_L3P_T0_DQS_AD1P_15-PadJ14)") (class "Default")
      (node (ref "U10F") (pin "J14") (pinfunction "IO_L3P_T0_DQS_AD1P_15_J14") (pintype "bidirectional"))
    )
    (net (code "230") (name "unconnected-(U10FB-IO_L4N_T0_15-PadG18)") (class "Default")
      (node (ref "U10F") (pin "G18") (pinfunction "IO_L4N_T0_15_G18") (pintype "bidirectional"))
    )
    (net (code "231") (name "unconnected-(U10FB-IO_L4P_T0_15-PadG17)") (class "Default")
      (node (ref "U10F") (pin "G17") (pinfunction "IO_L4P_T0_15_G17") (pintype "bidirectional"))
    )
    (net (code "232") (name "unconnected-(U10FB-IO_L5N_T0_AD9N_15-PadH15)") (class "Default")
      (node (ref "U10F") (pin "H15") (pinfunction "IO_L5N_T0_AD9N_15_H15") (pintype "bidirectional"))
    )
    (net (code "233") (name "unconnected-(U10FB-IO_L5P_T0_AD9P_15-PadJ15)") (class "Default")
      (node (ref "U10F") (pin "J15") (pinfunction "IO_L5P_T0_AD9P_15_J15") (pintype "bidirectional"))
    )
    (net (code "234") (name "unconnected-(U10FB-IO_L6N_T0_VREF_15-PadH18)") (class "Default")
      (node (ref "U10F") (pin "H18") (pinfunction "IO_L6N_T0_VREF_15_H18") (pintype "bidirectional"))
    )
    (net (code "235") (name "unconnected-(U10FB-IO_L6P_T0_15-PadH17)") (class "Default")
      (node (ref "U10F") (pin "H17") (pinfunction "IO_L6P_T0_15_H17") (pintype "bidirectional"))
    )
    (net (code "236") (name "unconnected-(U10FB-IO_L8P_T1_AD10P_15-PadH20)") (class "Default")
      (node (ref "U10F") (pin "H20") (pinfunction "IO_L8P_T1_AD10P_15_H20") (pintype "bidirectional"))
    )
    (net (code "237") (name "unconnected-(U10FB-IO_L12N_T1_MRCC_15-PadH19)") (class "Default")
      (node (ref "U10F") (pin "H19") (pinfunction "IO_L12N_T1_MRCC_15_H19") (pintype "bidirectional"))
    )
    (net (code "238") (name "unconnected-(U10FB-IO_L13N_T2_MRCC_15-PadK19)") (class "Default")
      (node (ref "U10F") (pin "K19") (pinfunction "IO_L13N_T2_MRCC_15_K19") (pintype "bidirectional"))
    )
    (net (code "239") (name "unconnected-(U10FB-IO_L13P_T2_MRCC_15-PadK18)") (class "Default")
      (node (ref "U10F") (pin "K18") (pinfunction "IO_L13P_T2_MRCC_15_K18") (pintype "bidirectional"))
    )
    (net (code "240") (name "unconnected-(U10FB-IO_L16N_T2_A27_15-PadL18)") (class "Default")
      (node (ref "U10F") (pin "L18") (pinfunction "IO_L16N_T2_A27_15_L18") (pintype "bidirectional"))
    )
    (net (code "241") (name "unconnected-(U10FB-IO_L16P_T2_A28_15-PadM18)") (class "Default")
      (node (ref "U10F") (pin "M18") (pinfunction "IO_L16P_T2_A28_15_M18") (pintype "bidirectional"))
    )
    (net (code "242") (name "unconnected-(U10FB-IO_L17N_T2_A25_15-PadN19)") (class "Default")
      (node (ref "U10F") (pin "N19") (pinfunction "IO_L17N_T2_A25_15_N19") (pintype "bidirectional"))
    )
    (net (code "243") (name "unconnected-(U10FB-IO_L17P_T2_A26_15-PadN18)") (class "Default")
      (node (ref "U10F") (pin "N18") (pinfunction "IO_L17P_T2_A26_15_N18") (pintype "bidirectional"))
    )
    (net (code "244") (name "unconnected-(U10FB-IO_L18N_T2_A23_15-PadM20)") (class "Default")
      (node (ref "U10F") (pin "M20") (pinfunction "IO_L18N_T2_A23_15_M20") (pintype "bidirectional"))
    )
    (net (code "245") (name "unconnected-(U10FB-IO_L19N_T3_A21_VREF_15-PadK14)") (class "Default")
      (node (ref "U10F") (pin "K14") (pinfunction "IO_L19N_T3_A21_VREF_15_K14") (pintype "bidirectional"))
    )
    (net (code "246") (name "unconnected-(U10FB-IO_L19P_T3_A22_15-PadK13)") (class "Default")
      (node (ref "U10F") (pin "K13") (pinfunction "IO_L19P_T3_A22_15_K13") (pintype "bidirectional"))
    )
    (net (code "247") (name "unconnected-(U10FB-IO_L20N_T3_A19_15-PadL13)") (class "Default")
      (node (ref "U10F") (pin "L13") (pinfunction "IO_L20N_T3_A19_15_L13") (pintype "bidirectional"))
    )
    (net (code "248") (name "unconnected-(U10FB-IO_L20P_T3_A20_15-PadM13)") (class "Default")
      (node (ref "U10F") (pin "M13") (pinfunction "IO_L20P_T3_A20_15_M13") (pintype "bidirectional"))
    )
    (net (code "249") (name "unconnected-(U10FB-IO_L21N_T3_DQS_A18_15-PadJ17)") (class "Default")
      (node (ref "U10F") (pin "J17") (pinfunction "IO_L21N_T3_DQS_A18_15_J17") (pintype "bidirectional"))
    )
    (net (code "250") (name "unconnected-(U10FB-IO_L21P_T3_DQS_15-PadK17)") (class "Default")
      (node (ref "U10F") (pin "K17") (pinfunction "IO_L21P_T3_DQS_15_K17") (pintype "bidirectional"))
    )
    (net (code "251") (name "unconnected-(U10FB-IO_L22N_T3_A16_15-PadL15)") (class "Default")
      (node (ref "U10F") (pin "L15") (pinfunction "IO_L22N_T3_A16_15_L15") (pintype "bidirectional"))
    )
    (net (code "252") (name "unconnected-(U10FB-IO_L22P_T3_A17_15-PadL14)") (class "Default")
      (node (ref "U10F") (pin "L14") (pinfunction "IO_L22P_T3_A17_15_L14") (pintype "bidirectional"))
    )
    (net (code "253") (name "unconnected-(U10FB-IO_L23N_T3_FWE_B_15-PadK16)") (class "Default")
      (node (ref "U10F") (pin "K16") (pinfunction "IO_L23N_T3_FWE_B_15_K16") (pintype "bidirectional"))
    )
    (net (code "254") (name "unconnected-(U10FB-IO_L23P_T3_FOE_B_15-PadL16)") (class "Default")
      (node (ref "U10F") (pin "L16") (pinfunction "IO_L23P_T3_FOE_B_15_L16") (pintype "bidirectional"))
    )
    (net (code "255") (name "unconnected-(U10FB-IO_L24N_T3_RS0_15-PadM16)") (class "Default")
      (node (ref "U10F") (pin "M16") (pinfunction "IO_L24N_T3_RS0_15_M16") (pintype "bidirectional"))
    )
    (net (code "256") (name "unconnected-(U10FB-IO_L24P_T3_RS1_15-PadM15)") (class "Default")
      (node (ref "U10F") (pin "M15") (pinfunction "IO_L24P_T3_RS1_15_M15") (pintype "bidirectional"))
    )
    (net (code "257") (name "unconnected-(U10FC-IO_0_16-PadF15)") (class "Default")
      (node (ref "U10F") (pin "F15") (pinfunction "IO_0_16_F15") (pintype "bidirectional"))
    )
    (net (code "258") (name "unconnected-(U10FC-IO_25_16-PadF21)") (class "Default")
      (node (ref "U10F") (pin "F21") (pinfunction "IO_25_16_F21") (pintype "bidirectional"))
    )
    (net (code "259") (name "unconnected-(U10FC-IO_L2N_T0_16-PadE17)") (class "Default")
      (node (ref "U10F") (pin "E17") (pinfunction "IO_L2N_T0_16_E17") (pintype "bidirectional"))
    )
    (net (code "260") (name "unconnected-(U10FC-IO_L2P_T0_16-PadF16)") (class "Default")
      (node (ref "U10F") (pin "F16") (pinfunction "IO_L2P_T0_16_F16") (pintype "bidirectional"))
    )
    (net (code "261") (name "unconnected-(U10FC-IO_L5N_T0_16-PadD16)") (class "Default")
      (node (ref "U10F") (pin "D16") (pinfunction "IO_L5N_T0_16_D16") (pintype "bidirectional"))
    )
    (net (code "262") (name "unconnected-(U10FC-IO_L5P_T0_16-PadE16)") (class "Default")
      (node (ref "U10F") (pin "E16") (pinfunction "IO_L5P_T0_16_E16") (pintype "bidirectional"))
    )
    (net (code "263") (name "unconnected-(U10FC-IO_L6P_T0_16-PadD14)") (class "Default")
      (node (ref "U10F") (pin "D14") (pinfunction "IO_L6P_T0_16_D14") (pintype "bidirectional"))
    )
    (net (code "264") (name "unconnected-(U10FC-IO_L8P_T1_16-PadC13)") (class "Default")
      (node (ref "U10F") (pin "C13") (pinfunction "IO_L8P_T1_16_C13") (pintype "bidirectional"))
    )
    (net (code "265") (name "unconnected-(U10FC-IO_L12P_T1_MRCC_16-PadD17)") (class "Default")
      (node (ref "U10F") (pin "D17") (pinfunction "IO_L12P_T1_MRCC_16_D17") (pintype "bidirectional"))
    )
    (net (code "266") (name "unconnected-(U10FC-IO_L15P_T2_DQS_16-PadF18)") (class "Default")
      (node (ref "U10F") (pin "F18") (pinfunction "IO_L15P_T2_DQS_16_F18") (pintype "bidirectional"))
    )
    (net (code "267") (name "unconnected-(U10FC-IO_L18P_T2_16-PadF19)") (class "Default")
      (node (ref "U10F") (pin "F19") (pinfunction "IO_L18P_T2_16_F19") (pintype "bidirectional"))
    )
    (net (code "268") (name "unconnected-(U10FC-IO_L19N_T3_VREF_16-PadC20)") (class "Default")
      (node (ref "U10F") (pin "C20") (pinfunction "IO_L19N_T3_VREF_16_C20") (pintype "bidirectional"))
    )
    (net (code "269") (name "unconnected-(U10FC-IO_L23N_T3_16-PadD21)") (class "Default")
      (node (ref "U10F") (pin "D21") (pinfunction "IO_L23N_T3_16_D21") (pintype "bidirectional"))
    )
    (net (code "270") (name "unconnected-(U10FC-IO_L23P_T3_16-PadE21)") (class "Default")
      (node (ref "U10F") (pin "E21") (pinfunction "IO_L23P_T3_16_E21") (pintype "bidirectional"))
    )
    (net (code "271") (name "unconnected-(U10FD-IO_0_34-PadT3)") (class "Default")
      (node (ref "U10F") (pin "T3") (pinfunction "IO_0_34_T3") (pintype "bidirectional"))
    )
    (net (code "272") (name "unconnected-(U10FD-IO_25_34-PadU7)") (class "Default")
      (node (ref "U10F") (pin "U7") (pinfunction "IO_25_34_U7") (pintype "bidirectional"))
    )
    (net (code "273") (name "unconnected-(U10FD-IO_L1N_T0_34-PadU1)") (class "Default")
      (node (ref "U10F") (pin "U1") (pinfunction "IO_L1N_T0_34_U1") (pintype "bidirectional"))
    )
    (net (code "274") (name "unconnected-(U10FD-IO_L1P_T0_34-PadT1)") (class "Default")
      (node (ref "U10F") (pin "T1") (pinfunction "IO_L1P_T0_34_T1") (pintype "bidirectional"))
    )
    (net (code "275") (name "unconnected-(U10FD-IO_L2P_T0_34-PadU2)") (class "Default")
      (node (ref "U10F") (pin "U2") (pinfunction "IO_L2P_T0_34_U2") (pintype "bidirectional"))
    )
    (net (code "276") (name "unconnected-(U10FD-IO_L4P_T0_34-PadW2)") (class "Default")
      (node (ref "U10F") (pin "W2") (pinfunction "IO_L4P_T0_34_W2") (pintype "bidirectional"))
    )
    (net (code "277") (name "unconnected-(U10FD-IO_L5P_T0_34-PadW1)") (class "Default")
      (node (ref "U10F") (pin "W1") (pinfunction "IO_L5P_T0_34_W1") (pintype "bidirectional"))
    )
    (net (code "278") (name "unconnected-(U10FD-IO_L6P_T0_34-PadU3)") (class "Default")
      (node (ref "U10F") (pin "U3") (pinfunction "IO_L6P_T0_34_U3") (pintype "bidirectional"))
    )
    (net (code "279") (name "unconnected-(U10FD-IO_L10P_T1_34-PadAA5)") (class "Default")
      (node (ref "U10F") (pin "AA5") (pinfunction "IO_L10P_T1_34_AA5") (pintype "bidirectional"))
    )
    (net (code "280") (name "unconnected-(U10FD-IO_L11N_T1_SRCC_34-PadAA4)") (class "Default")
      (node (ref "U10F") (pin "AA4") (pinfunction "IO_L11N_T1_SRCC_34_AA4") (pintype "bidirectional"))
    )
    (net (code "281") (name "unconnected-(U10FD-IO_L11P_T1_SRCC_34-PadY4)") (class "Default")
      (node (ref "U10F") (pin "Y4") (pinfunction "IO_L11P_T1_SRCC_34_Y4") (pintype "bidirectional"))
    )
    (net (code "282") (name "unconnected-(U10FD-IO_L13N_T2_MRCC_34-PadT4)") (class "Default")
      (node (ref "U10F") (pin "T4") (pinfunction "IO_L13N_T2_MRCC_34_T4") (pintype "bidirectional"))
    )
    (net (code "283") (name "unconnected-(U10FD-IO_L13P_T2_MRCC_34-PadR4)") (class "Default")
      (node (ref "U10F") (pin "R4") (pinfunction "IO_L13P_T2_MRCC_34_R4") (pintype "bidirectional"))
    )
    (net (code "284") (name "unconnected-(U10FD-IO_L14P_T2_SRCC_34-PadT5)") (class "Default")
      (node (ref "U10F") (pin "T5") (pinfunction "IO_L14P_T2_SRCC_34_T5") (pintype "bidirectional"))
    )
    (net (code "285") (name "unconnected-(U10FD-IO_L17N_T2_34-PadT6)") (class "Default")
      (node (ref "U10F") (pin "T6") (pinfunction "IO_L17N_T2_34_T6") (pintype "bidirectional"))
    )
    (net (code "286") (name "unconnected-(U10FD-IO_L17P_T2_34-PadR6)") (class "Default")
      (node (ref "U10F") (pin "R6") (pinfunction "IO_L17P_T2_34_R6") (pintype "bidirectional"))
    )
    (net (code "287") (name "unconnected-(U10FD-IO_L18N_T2_34-PadAA6)") (class "Default")
      (node (ref "U10F") (pin "AA6") (pinfunction "IO_L18N_T2_34_AA6") (pintype "bidirectional"))
    )
    (net (code "288") (name "unconnected-(U10FD-IO_L18P_T2_34-PadY6)") (class "Default")
      (node (ref "U10F") (pin "Y6") (pinfunction "IO_L18P_T2_34_Y6") (pintype "bidirectional"))
    )
    (net (code "289") (name "unconnected-(U10FD-IO_L20N_T3_34-PadAB6)") (class "Default")
      (node (ref "U10F") (pin "AB6") (pinfunction "IO_L20N_T3_34_AB6") (pintype "bidirectional"))
    )
    (net (code "290") (name "unconnected-(U10FD-IO_L20P_T3_34-PadAB7)") (class "Default")
      (node (ref "U10F") (pin "AB7") (pinfunction "IO_L20P_T3_34_AB7") (pintype "bidirectional"))
    )
    (net (code "291") (name "unconnected-(U10FD-IO_L22N_T3_34-PadAB8)") (class "Default")
      (node (ref "U10F") (pin "AB8") (pinfunction "IO_L22N_T3_34_AB8") (pintype "bidirectional"))
    )
    (net (code "292") (name "unconnected-(U10FD-IO_L22P_T3_34-PadAA8)") (class "Default")
      (node (ref "U10F") (pin "AA8") (pinfunction "IO_L22P_T3_34_AA8") (pintype "bidirectional"))
    )
    (net (code "293") (name "unconnected-(U10FE-IO_0_35-PadF4)") (class "Default")
      (node (ref "U10F") (pin "F4") (pinfunction "IO_0_35_F4") (pintype "bidirectional"))
    )
    (net (code "294") (name "unconnected-(U10FE-IO_25_35-PadL6)") (class "Default")
      (node (ref "U10F") (pin "L6") (pinfunction "IO_25_35_L6") (pintype "bidirectional"))
    )
    (net (code "295") (name "unconnected-(U10FE-IO_L12N_T1_MRCC_35-PadG4)") (class "Default")
      (node (ref "U10F") (pin "G4") (pinfunction "IO_L12N_T1_MRCC_35_G4") (pintype "bidirectional"))
    )
    (net (code "296") (name "unconnected-(U10FE-IO_L18N_T2_35-PadL4)") (class "Default")
      (node (ref "U10F") (pin "L4") (pinfunction "IO_L18N_T2_35_L4") (pintype "bidirectional"))
    )
    (net (code "297") (name "unconnected-(U10FL-NC-PadAA9)") (class "Default")
      (node (ref "U10F") (pin "AA9") (pinfunction "NC_AA9") (pintype "passive"))
    )
    (net (code "298") (name "unconnected-(U10FL-NC-PadAA10)") (class "Default")
      (node (ref "U10F") (pin "AA10") (pinfunction "NC_AA10") (pintype "passive"))
    )
    (net (code "299") (name "unconnected-(U10FL-NC-PadAA11)") (class "Default")
      (node (ref "U10F") (pin "AA11") (pinfunction "NC_AA11") (pintype "passive"))
    )
    (net (code "300") (name "unconnected-(U10FL-NC-PadAA13)") (class "Default")
      (node (ref "U10F") (pin "AA13") (pinfunction "NC_AA13") (pintype "passive"))
    )
    (net (code "301") (name "unconnected-(U10FL-NC-PadAA14)") (class "Default")
      (node (ref "U10F") (pin "AA14") (pinfunction "NC_AA14") (pintype "passive"))
    )
    (net (code "302") (name "unconnected-(U10FL-NC-PadAA15)") (class "Default")
      (node (ref "U10F") (pin "AA15") (pinfunction "NC_AA15") (pintype "passive"))
    )
    (net (code "303") (name "unconnected-(U10FL-NC-PadAA16)") (class "Default")
      (node (ref "U10F") (pin "AA16") (pinfunction "NC_AA16") (pintype "passive"))
    )
    (net (code "304") (name "unconnected-(U10FL-NC-PadAB10)") (class "Default")
      (node (ref "U10F") (pin "AB10") (pinfunction "NC_AB10") (pintype "passive"))
    )
    (net (code "305") (name "unconnected-(U10FL-NC-PadAB11)") (class "Default")
      (node (ref "U10F") (pin "AB11") (pinfunction "NC_AB11") (pintype "passive"))
    )
    (net (code "306") (name "unconnected-(U10FL-NC-PadAB12)") (class "Default")
      (node (ref "U10F") (pin "AB12") (pinfunction "NC_AB12") (pintype "passive"))
    )
    (net (code "307") (name "unconnected-(U10FL-NC-PadAB13)") (class "Default")
      (node (ref "U10F") (pin "AB13") (pinfunction "NC_AB13") (pintype "passive"))
    )
    (net (code "308") (name "unconnected-(U10FL-NC-PadAB15)") (class "Default")
      (node (ref "U10F") (pin "AB15") (pinfunction "NC_AB15") (pintype "passive"))
    )
    (net (code "309") (name "unconnected-(U10FL-NC-PadAB16)") (class "Default")
      (node (ref "U10F") (pin "AB16") (pinfunction "NC_AB16") (pintype "passive"))
    )
    (net (code "310") (name "unconnected-(U10FL-NC-PadAB17)") (class "Default")
      (node (ref "U10F") (pin "AB17") (pinfunction "NC_AB17") (pintype "passive"))
    )
    (net (code "311") (name "unconnected-(U10FL-NC-PadT14)") (class "Default")
      (node (ref "U10F") (pin "T14") (pinfunction "NC_T14") (pintype "passive"))
    )
    (net (code "312") (name "unconnected-(U10FL-NC-PadT15)") (class "Default")
      (node (ref "U10F") (pin "T15") (pinfunction "NC_T15") (pintype "passive"))
    )
    (net (code "313") (name "unconnected-(U10FL-NC-PadT16)") (class "Default")
      (node (ref "U10F") (pin "T16") (pinfunction "NC_T16") (pintype "passive"))
    )
    (net (code "314") (name "unconnected-(U10FL-NC-PadU15)") (class "Default")
      (node (ref "U10F") (pin "U15") (pinfunction "NC_U15") (pintype "passive"))
    )
    (net (code "315") (name "unconnected-(U10FL-NC-PadU16)") (class "Default")
      (node (ref "U10F") (pin "U16") (pinfunction "NC_U16") (pintype "passive"))
    )
    (net (code "316") (name "unconnected-(U10FL-NC-PadV10)") (class "Default")
      (node (ref "U10F") (pin "V10") (pinfunction "NC_V10") (pintype "passive"))
    )
    (net (code "317") (name "unconnected-(U10FL-NC-PadV13)") (class "Default")
      (node (ref "U10F") (pin "V13") (pinfunction "NC_V13") (pintype "passive"))
    )
    (net (code "318") (name "unconnected-(U10FL-NC-PadV14)") (class "Default")
      (node (ref "U10F") (pin "V14") (pinfunction "NC_V14") (pintype "passive"))
    )
    (net (code "319") (name "unconnected-(U10FL-NC-PadV15)") (class "Default")
      (node (ref "U10F") (pin "V15") (pinfunction "NC_V15") (pintype "passive"))
    )
    (net (code "320") (name "unconnected-(U10FL-NC-PadW10)") (class "Default")
      (node (ref "U10F") (pin "W10") (pinfunction "NC_W10") (pintype "passive"))
    )
    (net (code "321") (name "unconnected-(U10FL-NC-PadW11)") (class "Default")
      (node (ref "U10F") (pin "W11") (pinfunction "NC_W11") (pintype "passive"))
    )
    (net (code "322") (name "unconnected-(U10FL-NC-PadW12)") (class "Default")
      (node (ref "U10F") (pin "W12") (pinfunction "NC_W12") (pintype "passive"))
    )
    (net (code "323") (name "unconnected-(U10FL-NC-PadW14)") (class "Default")
      (node (ref "U10F") (pin "W14") (pinfunction "NC_W14") (pintype "passive"))
    )
    (net (code "324") (name "unconnected-(U10FL-NC-PadW15)") (class "Default")
      (node (ref "U10F") (pin "W15") (pinfunction "NC_W15") (pintype "passive"))
    )
    (net (code "325") (name "unconnected-(U10FL-NC-PadW16)") (class "Default")
      (node (ref "U10F") (pin "W16") (pinfunction "NC_W16") (pintype "passive"))
    )
    (net (code "326") (name "unconnected-(U10FL-NC-PadY11)") (class "Default")
      (node (ref "U10F") (pin "Y11") (pinfunction "NC_Y11") (pintype "passive"))
    )
    (net (code "327") (name "unconnected-(U10FL-NC-PadY12)") (class "Default")
      (node (ref "U10F") (pin "Y12") (pinfunction "NC_Y12") (pintype "passive"))
    )
    (net (code "328") (name "unconnected-(U10FL-NC-PadY13)") (class "Default")
      (node (ref "U10F") (pin "Y13") (pinfunction "NC_Y13") (pintype "passive"))
    )
    (net (code "329") (name "unconnected-(U10FL-NC-PadY14)") (class "Default")
      (node (ref "U10F") (pin "Y14") (pinfunction "NC_Y14") (pintype "passive"))
    )
    (net (code "330") (name "unconnected-(U10FL-NC-PadY16)") (class "Default")
      (node (ref "U10F") (pin "Y16") (pinfunction "NC_Y16") (pintype "passive"))
    )
    (net (code "331") (name "unconnected-(U10FL-NC-PadY17)") (class "Default")
      (node (ref "U10F") (pin "Y17") (pinfunction "NC_Y17") (pintype "passive"))
    )
  )
)
